# Mayfly_v1p1_revA.net
KiCad netlist of a schematic drawn in EAGLE
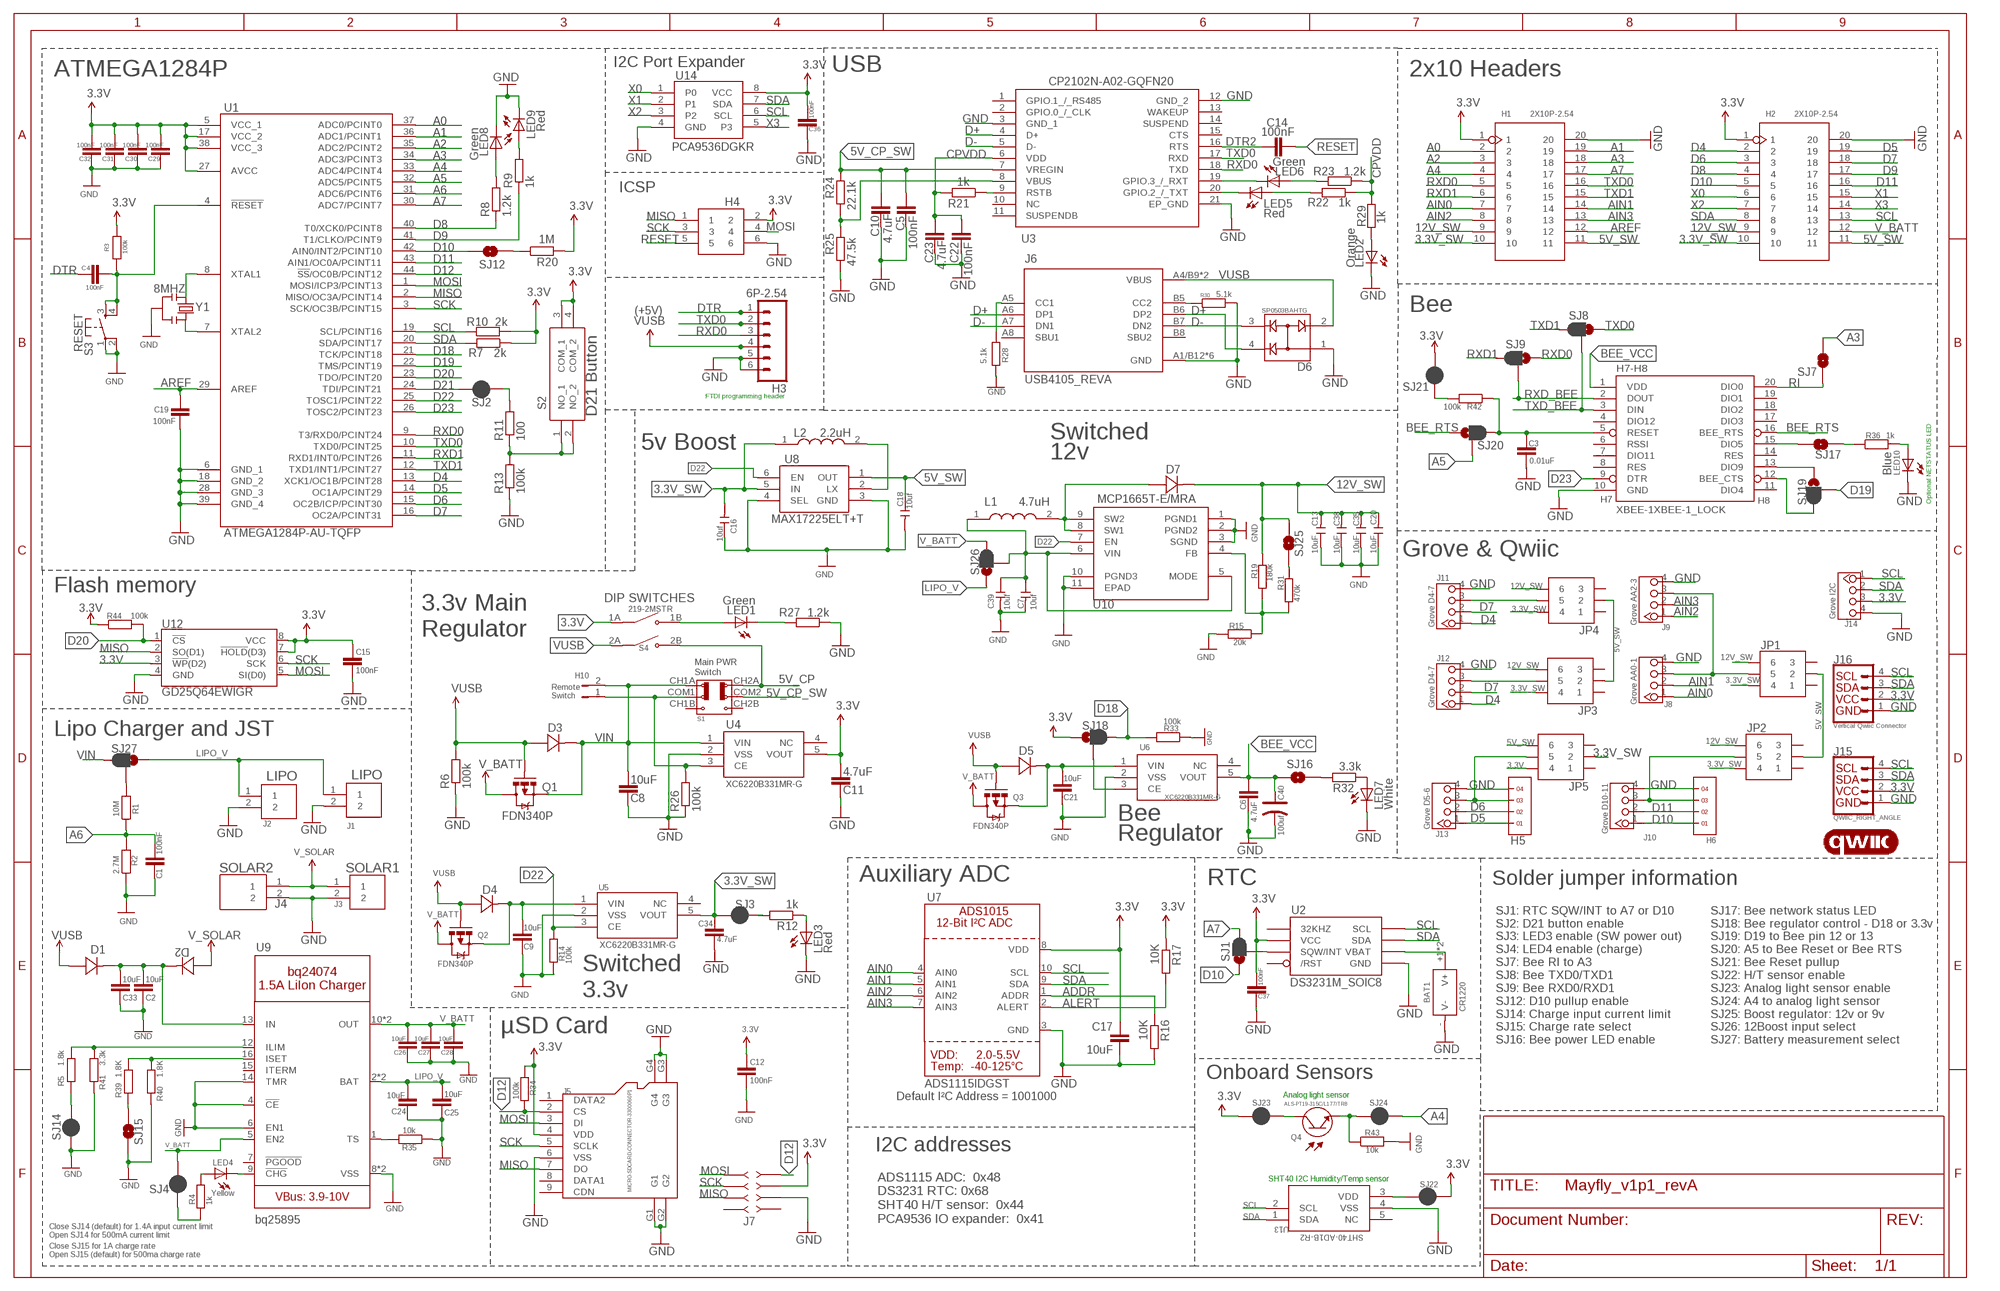
[diagram p0: schematic, sheet 1]

(export (version "E")
  (design (tool "Eeschema 10.0.6"))
  (components
    (comp (ref "BAT1")
      (value "CR1220")
      (footprint "eagle-import:BAT2P-13.5-CR1220")
      (libsource (lib "eagle-import") (part "DIP-BATTERY-CELL-HOLDER(1220)"))
    )
    (comp (ref "C1")
      (value "100nF")
      (footprint "eagle-import:C0603")
      (libsource (lib "eagle-import") (part "C_0603"))
    )
    (comp (ref "C2")
      (value "10uF")
      (footprint "eagle-import:C0603")
      (libsource (lib "eagle-import") (part "C_0603"))
    )
    (comp (ref "C3")
      (value "0.01uF")
      (footprint "eagle-import:C0603")
      (libsource (lib "eagle-import") (part "C_0603"))
    )
    (comp (ref "C4")
      (value "100nF")
      (footprint "eagle-import:C0603")
      (libsource (lib "eagle-import") (part "C_0603"))
    )
    (comp (ref "C5")
      (value "100nF")
      (footprint "eagle-import:C0603")
      (libsource (lib "eagle-import") (part "C_0603"))
    )
    (comp (ref "C6")
      (value "4.7uF")
      (footprint "eagle-import:C0603")
      (libsource (lib "eagle-import") (part "C_0603"))
    )
    (comp (ref "C7")
      (value "10uf")
      (footprint "eagle-import:C0805")
      (fields (field (name "MPN") "CC0805MKX5R5BB226"))
      (libsource (lib "eagle-import") (part "CERAMIC-22UF-6.3V-20%-X5R(0805)"))
    )
    (comp (ref "C8")
      (value "10uF")
      (footprint "eagle-import:C0603")
      (libsource (lib "eagle-import") (part "C_0603"))
    )
    (comp (ref "C9")
      (value "10uF")
      (footprint "eagle-import:C0603")
      (libsource (lib "eagle-import") (part "C_0603"))
    )
    (comp (ref "C10")
      (value "4.7uF")
      (footprint "eagle-import:C0603")
      (libsource (lib "eagle-import") (part "C_0603"))
    )
    (comp (ref "C11")
      (value "4.7uF")
      (footprint "eagle-import:C0603")
      (libsource (lib "eagle-import") (part "C_0603"))
    )
    (comp (ref "C12")
      (value "100nF")
      (footprint "eagle-import:C0603")
      (libsource (lib "eagle-import") (part "C_0603"))
    )
    (comp (ref "C13")
      (value "10uF")
      (footprint "eagle-import:C1206")
      (libsource (lib "eagle-import") (part "CERAMIC-22UF-16V-10%-X7R(1206)"))
    )
    (comp (ref "C14")
      (value "100nF")
      (footprint "eagle-import:C0603")
      (libsource (lib "eagle-import") (part "C_0603"))
    )
    (comp (ref "C15")
      (value "100nF")
      (footprint "eagle-import:C0402")
      (libsource (lib "eagle-import") (part "C_0402"))
    )
    (comp (ref "C16")
      (value "10uf")
      (footprint "eagle-import:C0603")
      (fields (field (name "MPN") "CC0603KRX5R6BB106"))
      (libsource (lib "eagle-import") (part "CERAMIC-10UF-10V-10%-X5R(0603)"))
    )
    (comp (ref "C17")
      (value "10uF")
      (footprint "eagle-import:C0603")
      (libsource (lib "eagle-import") (part "C_0603"))
    )
    (comp (ref "C18")
      (value "10uf")
      (footprint "eagle-import:C0603")
      (fields (field (name "MPN") "CC0603KRX5R6BB106"))
      (libsource (lib "eagle-import") (part "CERAMIC-10UF-10V-10%-X5R(0603)"))
    )
    (comp (ref "C19")
      (value "100nF")
      (footprint "eagle-import:C0402")
      (libsource (lib "eagle-import") (part "C_0402"))
    )
    (comp (ref "C20")
      (value "10uF")
      (footprint "eagle-import:C1206")
      (libsource (lib "eagle-import") (part "CERAMIC-22UF-16V-10%-X7R(1206)"))
    )
    (comp (ref "C21")
      (value "10uF")
      (footprint "eagle-import:C0603")
      (libsource (lib "eagle-import") (part "C_0603"))
    )
    (comp (ref "C22")
      (value "100nF")
      (footprint "eagle-import:C0603")
      (libsource (lib "eagle-import") (part "C_0603"))
    )
    (comp (ref "C23")
      (value "4.7uF")
      (footprint "eagle-import:C0603")
      (libsource (lib "eagle-import") (part "C_0603"))
    )
    (comp (ref "C24")
      (value "10uF")
      (footprint "eagle-import:C0603")
      (libsource (lib "eagle-import") (part "C_0603"))
    )
    (comp (ref "C25")
      (value "10uF")
      (footprint "eagle-import:C0603")
      (libsource (lib "eagle-import") (part "C_0603"))
    )
    (comp (ref "C26")
      (value "10uF")
      (footprint "eagle-import:C0603")
      (libsource (lib "eagle-import") (part "C_0603"))
    )
    (comp (ref "C27")
      (value "10uF")
      (footprint "eagle-import:C0603")
      (libsource (lib "eagle-import") (part "C_0603"))
    )
    (comp (ref "C28")
      (value "10uF")
      (footprint "eagle-import:C0603")
      (libsource (lib "eagle-import") (part "C_0603"))
    )
    (comp (ref "C29")
      (value "100nF")
      (footprint "eagle-import:C0603")
      (libsource (lib "eagle-import") (part "C_0603"))
    )
    (comp (ref "C30")
      (value "100nF")
      (footprint "eagle-import:C0603")
      (libsource (lib "eagle-import") (part "C_0603"))
    )
    (comp (ref "C31")
      (value "100nF")
      (footprint "eagle-import:C0603")
      (libsource (lib "eagle-import") (part "C_0603"))
    )
    (comp (ref "C32")
      (value "100nF")
      (footprint "eagle-import:C0603")
      (libsource (lib "eagle-import") (part "C_0603"))
    )
    (comp (ref "C33")
      (value "10uF")
      (footprint "eagle-import:C0603")
      (libsource (lib "eagle-import") (part "C_0603"))
    )
    (comp (ref "C34")
      (value "4.7uF")
      (footprint "eagle-import:C0603")
      (libsource (lib "eagle-import") (part "C_0603"))
    )
    (comp (ref "C35")
      (value "10uF")
      (footprint "eagle-import:C1206")
      (libsource (lib "eagle-import") (part "CERAMIC-22UF-16V-10%-X7R(1206)"))
    )
    (comp (ref "C36")
      (value "100nF")
      (footprint "eagle-import:C0603")
      (libsource (lib "eagle-import") (part "C_0603"))
    )
    (comp (ref "C37")
      (value "100nF")
      (footprint "eagle-import:C0603")
      (libsource (lib "eagle-import") (part "C_0603"))
    )
    (comp (ref "C38")
      (value "10uF")
      (footprint "eagle-import:C1206")
      (libsource (lib "eagle-import") (part "CERAMIC-22UF-16V-10%-X7R(1206)"))
    )
    (comp (ref "C39")
      (value "10uf")
      (footprint "eagle-import:C0805")
      (fields (field (name "MPN") "CC0805MKX5R5BB226"))
      (libsource (lib "eagle-import") (part "CERAMIC-22UF-6.3V-20%-X5R(0805)"))
    )
    (comp (ref "C40")
      (value "100uf")
      (footprint "eagle-import:AVX-B")
      (fields (field (name "MPN") "TAJB107M010#NJ"))
      (libsource (lib "eagle-import") (part "TANTALUM-SMD-100UF-10V(AVX-B)"))
    )
    (comp (ref "D1")
      (value "MSS2P2-M3/89A")
      (footprint "eagle-import:DIODE_MSP3V3")
      (libsource (lib "eagle-import") (part "MSS2P2-M3/89A"))
    )
    (comp (ref "D2")
      (value "MSS2P2-M3/89A")
      (footprint "eagle-import:DIODE_MSP3V3")
      (libsource (lib "eagle-import") (part "MSS2P2-M3/89A"))
    )
    (comp (ref "D3")
      (value "MSS2P2-M3/89A")
      (footprint "eagle-import:DIODE_MSP3V3")
      (libsource (lib "eagle-import") (part "MSS2P2-M3/89A"))
    )
    (comp (ref "D4")
      (value "MSS2P2-M3/89A")
      (footprint "eagle-import:DIODE_MSP3V3")
      (libsource (lib "eagle-import") (part "MSS2P2-M3/89A"))
    )
    (comp (ref "D5")
      (value "MSS2P2-M3/89A")
      (footprint "eagle-import:DIODE_MSP3V3")
      (libsource (lib "eagle-import") (part "MSS2P2-M3/89A"))
    )
    (comp (ref "D6")
      (value "SP0503BAHTG")
      (footprint "eagle-import:SOT143")
      (fields (field (name "DIGI-KEY_PART_NUMBER") "F2715CT-ND") (field (name "MF") "Littelfuse Inc."))
      (libsource (lib "eagle-import") (part "SP0503BAHTG"))
    )
    (comp (ref "D7")
      (value "MSS2P2-M3/89A")
      (footprint "eagle-import:DIODE_MSP3V3")
      (libsource (lib "eagle-import") (part "MSS2P2-M3/89A"))
    )
    (comp (ref "H1")
      (value "2X10P-2.54")
      (footprint "eagle-import:H2X10-2.54")
      (fields (field (name "MPN") "F185-1210A0BA1"))
      (libsource (lib "eagle-import") (part "DIP-BLACK-FEMALE-HEADER(2X10P-2.54)-2.54"))
    )
    (comp (ref "H2")
      (value "2X10P-2.54")
      (footprint "eagle-import:H2X10-2.54")
      (fields (field (name "MPN") "F185-1210A0BA1"))
      (libsource (lib "eagle-import") (part "DIP-BLACK-FEMALE-HEADER(2X10P-2.54)-2.54"))
    )
    (comp (ref "H3")
      (value "6P-2.54")
      (footprint "eagle-import:1X06_FEMALE_LOCK.010")
      (libsource (lib "eagle-import") (part "M06FEMALE_LOCK"))
    )
    (comp (ref "H4")
      (value "FTSH-103-01-F-D")
      (footprint "eagle-import:FTSH-103-XX-YYY")
      (fields (field (name "MOUSER_PART_NUMBER") "200-FTSH10301FD"))
      (libsource (lib "eagle-import") (part "FTSH-103-01-F-D"))
    )
    (comp (ref "H5")
      (value "1X4")
      (footprint "eagle-import:1X4")
      (libsource (lib "eagle-import") (part "1X4"))
    )
    (comp (ref "H6")
      (value "1X4")
      (footprint "eagle-import:1X4")
      (libsource (lib "eagle-import") (part "1X4"))
    )
    (comp (ref "H7-H8")
      (value "XBEE-1XBEE-1_LOCK")
      (footprint "eagle-import:XBEE-1_LOCK")
      (libsource (lib "eagle-import") (part "XBEE-1XBEE-1_LOCK"))
    )
    (comp (ref "H10")
      (value "JUMPER-PTH-2-NO")
      (footprint "eagle-import:PTH-JUMPER-2-NO_NO_SILK")
      (libsource (lib "eagle-import") (part "JUMPER-PTH-2-NO"))
    )
    (comp (ref "J1")
      (value "JST_EPH_2PIN")
      (footprint "eagle-import:JST_EPH_B2B-PH-K-S")
      (libsource (lib "eagle-import") (part "JST_EPH_2PIN"))
    )
    (comp (ref "J2")
      (value "JST_EPH_2PIN")
      (footprint "eagle-import:JST_EPH_B2B-PH-K-S")
      (libsource (lib "eagle-import") (part "JST_EPH_2PIN"))
    )
    (comp (ref "J3")
      (value "JST_EPH_2PIN")
      (footprint "eagle-import:JST_EPH_B2B-PH-K-S")
      (libsource (lib "eagle-import") (part "JST_EPH_2PIN"))
    )
    (comp (ref "J4")
      (value "1778557")
      (footprint "eagle-import:SHDR2W70P0X250_1X2_670X500X765")
      (fields (field (name "MOUSER_PART_NUMBER") "651-1778557"))
      (libsource (lib "eagle-import") (part "1778557"))
    )
    (comp (ref "J5")
      (value "MICRO-SDCARD-CONNECTOR-3300060P1")
      (footprint "eagle-import:9P-SMD-W-RING")
      (libsource (lib "eagle-import") (part "MICRO-SDCARD-CONNECTOR-3300060P1"))
    )
    (comp (ref "J6")
      (value "USB4105_REVA")
      (footprint "eagle-import:GCT_USB4105_REVA")
      (fields (field (name "MF") "Global Connector Technology") (field (name "MP") "USB4105"))
      (libsource (lib "eagle-import") (part "USB4105_REVA"))
    )
    (comp (ref "J7")
      (value "79107-08_S")
      (footprint "eagle-import:79107-08")
      (libsource (lib "eagle-import") (part "79107-08_S"))
    )
    (comp (ref "J8")
      (value "Grove AA0-1")
      (footprint "eagle-import:HW4-2.0")
      (libsource (lib "eagle-import") (part "GROVE-CONNECTOR-DIP(4P-2.0)"))
    )
    (comp (ref "J9")
      (value "Grove AA2-3")
      (footprint "eagle-import:HW4-2.0")
      (libsource (lib "eagle-import") (part "GROVE-CONNECTOR-DIP(4P-2.0)"))
    )
    (comp (ref "J10")
      (value "Grove D10-11")
      (footprint "eagle-import:HW4-2.0")
      (libsource (lib "eagle-import") (part "GROVE-CONNECTOR-DIP(4P-2.0)"))
    )
    (comp (ref "J11")
      (value "Grove D4-7")
      (footprint "eagle-import:HW4-2.0")
      (libsource (lib "eagle-import") (part "GROVE-CONNECTOR-DIP(4P-2.0)"))
    )
    (comp (ref "J12")
      (value "Grove D4-7")
      (footprint "eagle-import:HW4-2.0")
      (libsource (lib "eagle-import") (part "GROVE-CONNECTOR-DIP(4P-2.0)"))
    )
    (comp (ref "J13")
      (value "Grove D5-6")
      (footprint "eagle-import:HW4-2.0")
      (libsource (lib "eagle-import") (part "GROVE-CONNECTOR-DIP(4P-2.0)"))
    )
    (comp (ref "J14")
      (value "Grove I2C")
      (footprint "eagle-import:HW4-2.0")
      (libsource (lib "eagle-import") (part "GROVE-CONNECTOR-DIP(4P-2.0)"))
    )
    (comp (ref "J15")
      (value "QWIIC_RIGHT_ANGLE")
      (footprint "eagle-import:JST04_1MM_RA")
      (libsource (lib "eagle-import") (part "QWIIC_CONNECTORJS-1MM"))
    )
    (comp (ref "J16")
      (value "Vertical Qwiic Connector")
      (footprint "eagle-import:JST04_1MM_VERT")
      (libsource (lib "eagle-import") (part "QWIIC_CONNECTOR"))
    )
    (comp (ref "JP1")
      (value "M22-2520305")
      (footprint "eagle-import:HDRV6W50P200_2X3_600X400X525P")
      (fields (field (name "MOUSER_PART_NUMBER") "855-M22-2520305"))
      (libsource (lib "eagle-import") (part "M22-2520305"))
    )
    (comp (ref "JP2")
      (value "M22-2520305")
      (footprint "eagle-import:HDRV6W50P200_2X3_600X400X525P")
      (fields (field (name "MOUSER_PART_NUMBER") "855-M22-2520305"))
      (libsource (lib "eagle-import") (part "M22-2520305"))
    )
    (comp (ref "JP3")
      (value "M22-2520305")
      (footprint "eagle-import:HDRV6W50P200_2X3_600X400X525P")
      (fields (field (name "MOUSER_PART_NUMBER") "855-M22-2520305"))
      (libsource (lib "eagle-import") (part "M22-2520305"))
    )
    (comp (ref "JP4")
      (value "M22-2520305")
      (footprint "eagle-import:HDRV6W50P200_2X3_600X400X525P")
      (fields (field (name "MOUSER_PART_NUMBER") "855-M22-2520305"))
      (libsource (lib "eagle-import") (part "M22-2520305"))
    )
    (comp (ref "JP5")
      (value "M22-2520305")
      (footprint "eagle-import:HDRV6W50P200_2X3_600X400X525P")
      (fields (field (name "MOUSER_PART_NUMBER") "855-M22-2520305"))
      (libsource (lib "eagle-import") (part "M22-2520305"))
    )
    (comp (ref "L1")
      (value "4.7uH")
      (footprint "eagle-import:XAL4030472MEC")
      (fields
        (field (name "MANUFACTURER_PART_NUMBER") "XAL4030-472MEC")
        (field (name "MOUSER_PART_NUMBER") "994-XAL4030-472MEC")
      )
      (libsource (lib "eagle-import") (part "XAL4030-472MEC"))
    )
    (comp (ref "L2")
      (value "2.2uH")
      (footprint "eagle-import:1285ASH1R0MP2")
      (fields
        (field (name "MANUFACTURER_PART_NUMBER") "DFE201610E-2R2M=P2")
        (field (name "MOUSER_PART_NUMBER") "81-DFE201610E-2R2MP2")
      )
      (libsource (lib "eagle-import") (part "DFE201610E-2R2M=P2"))
    )
    (comp (ref "LED1")
      (value "Green")
      (footprint "eagle-import:LED-0603")
      (libsource (lib "eagle-import") (part "LED0603"))
    )
    (comp (ref "LED2")
      (value "Orange")
      (footprint "eagle-import:LED-0603")
      (libsource (lib "eagle-import") (part "LED0603"))
    )
    (comp (ref "LED3")
      (value "Red")
      (footprint "eagle-import:LED-0603")
      (libsource (lib "eagle-import") (part "LED0603"))
    )
    (comp (ref "LED4")
      (value "Yellow")
      (footprint "eagle-import:LED-0603")
      (libsource (lib "eagle-import") (part "LED0603"))
    )
    (comp (ref "LED5")
      (value "Red")
      (footprint "eagle-import:LED-0603")
      (libsource (lib "eagle-import") (part "LED0603"))
    )
    (comp (ref "LED6")
      (value "Green")
      (footprint "eagle-import:LED-0603")
      (libsource (lib "eagle-import") (part "LED0603"))
    )
    (comp (ref "LED7")
      (value "White")
      (footprint "eagle-import:LED-0603")
      (libsource (lib "eagle-import") (part "LED0603"))
    )
    (comp (ref "LED8")
      (value "Green")
      (footprint "eagle-import:LED-0603")
      (libsource (lib "eagle-import") (part "LED0603"))
    )
    (comp (ref "LED9")
      (value "Red")
      (footprint "eagle-import:LED-0603")
      (libsource (lib "eagle-import") (part "LED0603"))
    )
    (comp (ref "LED10")
      (value "Blue")
      (footprint "eagle-import:LED-0603")
      (libsource (lib "eagle-import") (part "LED0603"))
    )
    (comp (ref "LOGO4")
      (value "QWIIC_LOGO_5MM")
      (footprint "eagle-import:QWIIC_5MM")
      (libsource (lib "eagle-import") (part "QWIIC_LOGO_5MM"))
    )
    (comp (ref "Q1")
      (value "FDN340P")
      (footprint "eagle-import:SOT23-S-PADS")
      (libsource (lib "eagle-import") (part "MOSFET-P-CHANNELSMALL"))
    )
    (comp (ref "Q2")
      (value "FDN340P")
      (footprint "eagle-import:SOT23-S-PADS")
      (libsource (lib "eagle-import") (part "MOSFET-P-CHANNELSMALL"))
    )
    (comp (ref "Q3")
      (value "FDN340P")
      (footprint "eagle-import:SOT23-S-PADS")
      (libsource (lib "eagle-import") (part "MOSFET-P-CHANNELSMALL"))
    )
    (comp (ref "Q4")
      (value "ALS-PT19-315C/L177/TR8")
      (footprint "eagle-import:XDCR_ALS-PT19-315C_L177_TR8")
      (fields (field (name "MF") "Everlight"))
      (libsource (lib "eagle-import") (part "ALS-PT19-315C/L177/TR8"))
    )
    (comp (ref "R1")
      (value "10M")
      (footprint "eagle-import:R0402")
      (libsource (lib "eagle-import") (part "R_0402"))
    )
    (comp (ref "R2")
      (value "2.7M")
      (footprint "eagle-import:R0402")
      (libsource (lib "eagle-import") (part "R_0402"))
    )
    (comp (ref "R3")
      (value "100k")
      (footprint "eagle-import:R0603")
      (libsource (lib "eagle-import") (part "R_0603"))
    )
    (comp (ref "R4")
      (value "1k")
      (footprint "eagle-import:R0402")
      (libsource (lib "eagle-import") (part "R_0402"))
    )
    (comp (ref "R5")
      (value "1.8k")
      (footprint "eagle-import:R0402")
      (libsource (lib "eagle-import") (part "R_0402"))
    )
    (comp (ref "R6")
      (value "100k")
      (footprint "eagle-import:R0402")
      (libsource (lib "eagle-import") (part "R_0402"))
    )
    (comp (ref "R7")
      (value "2k")
      (footprint "eagle-import:R0603")
      (libsource (lib "eagle-import") (part "R_0603"))
    )
    (comp (ref "R8")
      (value "1.2k")
      (footprint "eagle-import:R0402")
      (libsource (lib "eagle-import") (part "R_0402"))
    )
    (comp (ref "R9")
      (value "1k")
      (footprint "eagle-import:R0402")
      (libsource (lib "eagle-import") (part "R_0402"))
    )
    (comp (ref "R10")
      (value "2k")
      (footprint "eagle-import:R0603")
      (libsource (lib "eagle-import") (part "R_0603"))
    )
    (comp (ref "R11")
      (value "100")
      (footprint "eagle-import:R0402")
      (libsource (lib "eagle-import") (part "R_0402"))
    )
    (comp (ref "R12")
      (value "1k")
      (footprint "eagle-import:R0402")
      (libsource (lib "eagle-import") (part "R_0402"))
    )
    (comp (ref "R13")
      (value "100k")
      (footprint "eagle-import:R0402")
      (libsource (lib "eagle-import") (part "R_0402"))
    )
    (comp (ref "R14")
      (value "100k")
      (footprint "eagle-import:R0402")
      (libsource (lib "eagle-import") (part "R_0402"))
    )
    (comp (ref "R15")
      (value "20k")
      (footprint "eagle-import:R0402")
      (libsource (lib "eagle-import") (part "R_0402"))
    )
    (comp (ref "R16")
      (value "10K")
      (footprint "eagle-import:R0402")
      (libsource (lib "eagle-import") (part "R_0402"))
    )
    (comp (ref "R17")
      (value "10K")
      (footprint "eagle-import:R0402")
      (libsource (lib "eagle-import") (part "R_0402"))
    )
    (comp (ref "R19")
      (value "180k")
      (footprint "eagle-import:R0402")
      (libsource (lib "eagle-import") (part "R_0402"))
    )
    (comp (ref "R20")
      (value "1M")
      (footprint "eagle-import:R0603")
      (libsource (lib "eagle-import") (part "R_0603"))
    )
    (comp (ref "R21")
      (value "1k")
      (footprint "eagle-import:R0402")
      (libsource (lib "eagle-import") (part "R_0402"))
    )
    (comp (ref "R22")
      (value "1k")
      (footprint "eagle-import:R0402")
      (libsource (lib "eagle-import") (part "R_0402"))
    )
    (comp (ref "R23")
      (value "1.2k")
      (footprint "eagle-import:R0402")
      (libsource (lib "eagle-import") (part "R_0402"))
    )
    (comp (ref "R24")
      (value "22.1k")
      (footprint "eagle-import:R0402")
      (libsource (lib "eagle-import") (part "R_0402"))
    )
    (comp (ref "R25")
      (value "47.5k")
      (footprint "eagle-import:R0402")
      (libsource (lib "eagle-import") (part "R_0402"))
    )
    (comp (ref "R26")
      (value "100k")
      (footprint "eagle-import:R0603")
      (libsource (lib "eagle-import") (part "R_0603"))
    )
    (comp (ref "R27")
      (value "1.2k")
      (footprint "eagle-import:R0402")
      (libsource (lib "eagle-import") (part "R_0402"))
    )
    (comp (ref "R28")
      (value "5.1k")
      (footprint "eagle-import:R0402")
      (libsource (lib "eagle-import") (part "R_0402"))
    )
    (comp (ref "R29")
      (value "1k")
      (footprint "eagle-import:R0402")
      (libsource (lib "eagle-import") (part "R_0402"))
    )
    (comp (ref "R30")
      (value "5.1k")
      (footprint "eagle-import:R0402")
      (libsource (lib "eagle-import") (part "R_0402"))
    )
    (comp (ref "R31")
      (value "470k")
      (footprint "eagle-import:R0402")
      (libsource (lib "eagle-import") (part "R_0402"))
    )
    (comp (ref "R32")
      (value "3.3k")
      (footprint "eagle-import:R0402")
      (libsource (lib "eagle-import") (part "R_0402"))
    )
    (comp (ref "R33")
      (value "100k")
      (footprint "eagle-import:R0402")
      (libsource (lib "eagle-import") (part "R_0402"))
    )
    (comp (ref "R34")
      (value "100k")
      (footprint "eagle-import:R0402")
      (libsource (lib "eagle-import") (part "R_0402"))
    )
    (comp (ref "R35")
      (value "10k")
      (footprint "eagle-import:R0402")
      (libsource (lib "eagle-import") (part "R_0402"))
    )
    (comp (ref "R36")
      (value "1k")
      (footprint "eagle-import:R0402")
      (libsource (lib "eagle-import") (part "R_0402"))
    )
    (comp (ref "R39")
      (value "1.8K")
      (footprint "eagle-import:R0402")
      (libsource (lib "eagle-import") (part "R_0402"))
    )
    (comp (ref "R40")
      (value "1.8K")
      (footprint "eagle-import:R0402")
      (libsource (lib "eagle-import") (part "R_0402"))
    )
    (comp (ref "R41")
      (value "3.3k")
      (footprint "eagle-import:R0402")
      (libsource (lib "eagle-import") (part "R_0402"))
    )
    (comp (ref "R42")
      (value "100k")
      (footprint "eagle-import:R0402")
      (libsource (lib "eagle-import") (part "R_0402"))
    )
    (comp (ref "R43")
      (value "10k")
      (footprint "eagle-import:R0402")
      (libsource (lib "eagle-import") (part "R_0402"))
    )
    (comp (ref "R44")
      (value "100k")
      (footprint "eagle-import:R0402")
      (libsource (lib "eagle-import") (part "R_0402"))
    )
    (comp (ref "S1")
      (value "SWITCH-2CH-6P-3010010P1")
      (footprint "eagle-import:6P-2CH-2.54-9.1X3.5X3.2+2H")
      (libsource (lib "eagle-import") (part "SWITCH-2CH-6P-3010010P1"))
    )
    (comp (ref "S2")
      (value "PTS647SK38SMTR2LFS")
      (footprint "eagle-import:PTS647SK38SMTR2LFS")
      (fields (field (name "MOUSER_PART_NUMBER") "611-PTS647SK38SMTR2L"))
      (libsource (lib "eagle-import") (part "PTS647SK38SMTR2LFS"))
    )
    (comp (ref "S3")
      (value "MOMENTARY-SWITCH-SPST-2-SMD-4.6X2.8MM")
      (footprint "eagle-import:TACTILE_SWITCH_SMD_4.6X2.8MM")
      (libsource (lib "eagle-import") (part "MOMENTARY-SWITCH-SPST-2-SMD-4.6X2.8MM"))
    )
    (comp (ref "S4")
      (value "219-2MSTR")
      (footprint "eagle-import:SW_219-2MSTR")
      (fields (field (name "DIGI-KEY_PART_NUMBER") "CT3114CT-ND") (field (name "MF") "CTS Electrocomponents"))
      (libsource (lib "eagle-import") (part "219-2MSTR"))
    )
    (comp (ref "SJ1")
      (value "JUMPER-SMT_3_1-NC_PASTE_SILK")
      (footprint "eagle-import:SMT-JUMPER_3_1-NC_PASTE_SILK")
      (libsource (lib "eagle-import") (part "JUMPER-SMT_3_1-NC_PASTE_SILK"))
    )
    (comp (ref "SJ2")
      (value "JUMPER-SMT_2_NC_PASTE_SILK")
      (footprint "eagle-import:SMT-JUMPER_2_NC_PASTE_SILK")
      (libsource (lib "eagle-import") (part "JUMPER-SMT_2_NC_PASTE_SILK"))
    )
    (comp (ref "SJ3")
      (value "JUMPER-SMT_2_NC_PASTE_SILK")
      (footprint "eagle-import:SMT-JUMPER_2_NC_PASTE_SILK")
      (libsource (lib "eagle-import") (part "JUMPER-SMT_2_NC_PASTE_SILK"))
    )
    (comp (ref "SJ4")
      (value "JUMPER-SMT_2_NC_PASTE_SILK")
      (footprint "eagle-import:SMT-JUMPER_2_NC_PASTE_SILK")
      (libsource (lib "eagle-import") (part "JUMPER-SMT_2_NC_PASTE_SILK"))
    )
    (comp (ref "SJ7")
      (value "JUMPER-SMT_2_NO_SILK")
      (footprint "eagle-import:SMT-JUMPER_2_NO_SILK")
      (libsource (lib "eagle-import") (part "JUMPER-SMT_2_NO_SILK"))
    )
    (comp (ref "SJ8")
      (value "JUMPER-SMT_3_1-NC_PASTE_SILK")
      (footprint "eagle-import:SMT-JUMPER_3_1-NC_PASTE_SILK")
      (libsource (lib "eagle-import") (part "JUMPER-SMT_3_1-NC_PASTE_SILK"))
    )
    (comp (ref "SJ9")
      (value "JUMPER-SMT_3_1-NC_PASTE_SILK")
      (footprint "eagle-import:SMT-JUMPER_3_1-NC_PASTE_SILK")
      (libsource (lib "eagle-import") (part "JUMPER-SMT_3_1-NC_PASTE_SILK"))
    )
    (comp (ref "SJ12")
      (value "SOLDERJUMPERNO")
      (footprint "eagle-import:SJ_2S-NO")
      (libsource (lib "eagle-import") (part "SOLDERJUMPERNO"))
    )
    (comp (ref "SJ14")
      (value "JUMPER-SMT_2_NC_PASTE_SILK")
      (footprint "eagle-import:SMT-JUMPER_2_NC_PASTE_SILK")
      (libsource (lib "eagle-import") (part "JUMPER-SMT_2_NC_PASTE_SILK"))
    )
    (comp (ref "SJ15")
      (value "JUMPER-SMT_2_NO_SILK")
      (footprint "eagle-import:SMT-JUMPER_2_NO_SILK")
      (libsource (lib "eagle-import") (part "JUMPER-SMT_2_NO_SILK"))
    )
    (comp (ref "SJ16")
      (value "JUMPER-SMT_2_NO_SILK")
      (footprint "eagle-import:SMT-JUMPER_2_NO_SILK")
      (libsource (lib "eagle-import") (part "JUMPER-SMT_2_NO_SILK"))
    )
    (comp (ref "SJ17")
      (value "JUMPER-SMT_2_NO_SILK")
      (footprint "eagle-import:SMT-JUMPER_2_NO_SILK")
      (libsource (lib "eagle-import") (part "JUMPER-SMT_2_NO_SILK"))
    )
    (comp (ref "SJ18")
      (value "JUMPER-SMT_3_1-NC_PASTE_SILK")
      (footprint "eagle-import:SMT-JUMPER_3_1-NC_PASTE_SILK")
      (libsource (lib "eagle-import") (part "JUMPER-SMT_3_1-NC_PASTE_SILK"))
    )
    (comp (ref "SJ19")
      (value "JUMPER-SMT_3_1-NC_PASTE_SILK")
      (footprint "eagle-import:SMT-JUMPER_3_1-NC_PASTE_SILK")
      (libsource (lib "eagle-import") (part "JUMPER-SMT_3_1-NC_PASTE_SILK"))
    )
    (comp (ref "SJ20")
      (value "JUMPER-SMT_3_1-NC_PASTE_SILK")
      (footprint "eagle-import:SMT-JUMPER_3_1-NC_PASTE_SILK")
      (libsource (lib "eagle-import") (part "JUMPER-SMT_3_1-NC_PASTE_SILK"))
    )
    (comp (ref "SJ21")
      (value "JUMPER-SMT_2_NC_PASTE_SILK")
      (footprint "eagle-import:SMT-JUMPER_2_NC_PASTE_SILK")
      (libsource (lib "eagle-import") (part "JUMPER-SMT_2_NC_PASTE_SILK"))
    )
    (comp (ref "SJ22")
      (value "JUMPER-SMT_2_NC_PASTE_SILK")
      (footprint "eagle-import:SMT-JUMPER_2_NC_PASTE_SILK")
      (libsource (lib "eagle-import") (part "JUMPER-SMT_2_NC_PASTE_SILK"))
    )
    (comp (ref "SJ23")
      (value "JUMPER-SMT_2_NC_PASTE_SILK")
      (footprint "eagle-import:SMT-JUMPER_2_NC_PASTE_SILK")
      (libsource (lib "eagle-import") (part "JUMPER-SMT_2_NC_PASTE_SILK"))
    )
    (comp (ref "SJ24")
      (value "JUMPER-SMT_2_NC_PASTE_SILK")
      (footprint "eagle-import:SMT-JUMPER_2_NC_PASTE_SILK")
      (libsource (lib "eagle-import") (part "JUMPER-SMT_2_NC_PASTE_SILK"))
    )
    (comp (ref "SJ25")
      (value "JUMPER-SMT_2_NO_SILK")
      (footprint "eagle-import:SMT-JUMPER_2_NO_SILK")
      (libsource (lib "eagle-import") (part "JUMPER-SMT_2_NO_SILK"))
    )
    (comp (ref "SJ26")
      (value "JUMPER-SMT_3_1-NC_PASTE_SILK")
      (footprint "eagle-import:SMT-JUMPER_3_1-NC_PASTE_SILK")
      (libsource (lib "eagle-import") (part "sdh_SparkFun-Jumpers_JUMPER-SMT_3_1-NC_PASTE_SILK"))
    )
    (comp (ref "SJ27")
      (value "JUMPER-SMT_3_1-NC_PASTE_SILK")
      (footprint "eagle-import:SMT-JUMPER_3_1-NC_PASTE_SILK")
      (libsource (lib "eagle-import") (part "JUMPER-SMT_3_1-NC_PASTE_SILK"))
    )
    (comp (ref "U1")
      (value "ATMEGA1284P-AU-TQFP")
      (footprint "eagle-import:QFP80P1200X1200X120-44N")
      (fields
        (field (name "MANUFACTURER_PART_NUMBER") "ATMEGA1284P-AU")
        (field (name "MOUSER_PART_NUMBER") "556-ATMEGA1284P-AU")
      )
      (libsource (lib "eagle-import") (part "ATMEGA1284P-AU-TQFP"))
    )
    (comp (ref "U2")
      (value "DS3231M_SOIC8")
      (footprint "eagle-import:SO8")
      (libsource (lib "eagle-import") (part "DS3231M_SOIC8"))
    )
    (comp (ref "U3")
      (value "CP2102N-A02-GQFN20")
      (footprint "eagle-import:CP2102NA02GQFN20")
      (fields (field (name "MOUSER_PART_NUMBER") "634-CP2102NA02GQFN20"))
      (libsource (lib "eagle-import") (part "CP2102N-A02-GQFN20"))
    )
    (comp (ref "U4")
      (value "XC6220B331MR-G")
      (footprint "eagle-import:SOT95P280X130-5N")
      (fields (field (name "MOUSER_PART_NUMBER") "865-XC6220B331MR-G"))
      (libsource (lib "eagle-import") (part "XC6220B331MR-G"))
    )
    (comp (ref "U5")
      (value "XC6220B331MR-G")
      (footprint "eagle-import:SOT95P280X130-5N")
      (fields (field (name "MOUSER_PART_NUMBER") "865-XC6220B331MR-G"))
      (libsource (lib "eagle-import") (part "XC6220B331MR-G"))
    )
    (comp (ref "U6")
      (value "XC6220B331MR-G")
      (footprint "eagle-import:SOT95P280X130-5N")
      (fields (field (name "MOUSER_PART_NUMBER") "865-XC6220B331MR-G"))
      (libsource (lib "eagle-import") (part "XC6220B331MR-G"))
    )
    (comp (ref "U7")
      (value "ADS1115IDGST")
      (footprint "eagle-import:MSOP10")
      (libsource (lib "eagle-import") (part "ADC_ADS1015"))
    )
    (comp (ref "U8")
      (value "MAX17225ELT+T")
      (footprint "eagle-import:MAX17225ELTT")
      (fields (field (name "MOUSER_PART_NUMBER") "700-MAX17225ELT+T"))
      (libsource (lib "eagle-import") (part "MAX17225ELT+T"))
    )
    (comp (ref "U9")
      (value "ADAFRUIT_POWER_BQ24074")
      (footprint "eagle-import:ADAFRUIT_POWER_QFN16_3MM")
      (libsource (lib "eagle-import") (part "ADAFRUIT_POWER_BQ24074"))
    )
    (comp (ref "U10")
      (value "MCP1665T-E/MRA")
      (footprint "eagle-import:QFN50P200X200X90-11N")
      (libsource (lib "eagle-import") (part "MCP1665T-E/MRA"))
    )
    (comp (ref "U12")
      (value "GD25Q64EWIGR")
      (footprint "eagle-import:WSON8-6X5MM")
      (libsource (lib "eagle-import") (part "W25Q32FVZP"))
    )
    (comp (ref "U13")
      (value "SHT40-AD1B-R2")
      (footprint "eagle-import:SHT4X_SEN")
      (fields (field (name "COPYRIGHT") "Copyright (C) 2018 Accelerated Designs. All rights reserved"))
      (libsource (lib "eagle-import") (part "SHT40-AD1B-R2"))
    )
    (comp (ref "U14")
      (value "PCA9536DGKR")
      (footprint "eagle-import:SOP65P490X110-8N")
      (fields (field (name "MOUSER_PART_NUMBER") "595-PCA9536DGKR"))
      (libsource (lib "eagle-import") (part "PCA9536DGKR"))
    )
    (comp (ref "Y1")
      (value "8MHZ")
      (footprint "eagle-import:X3-SMD-3.6X1.3X0.8MM")
      (fields (field (name "MPN") "CSTCE8M00G15L99-R0"))
      (libsource (lib "eagle-import") (part "SMD-RESONATOR-8MHZ-33PF-0.1%(3P-3.2X1.3MM)"))
    )
  )
  (nets
    (net (code "1") (name "/5V_CP") (class "Default")
      (node (ref "S1") (pin "CH2A") (pinfunction "CH2A_CH2A") (pintype "bidirectional"))
      (node (ref "S4") (pin "2B") (pinfunction "NO2_2B") (pintype "passive"))
    )
    (net (code "2") (name "/A0") (class "Default")
      (node (ref "H1") (pin "2") (pinfunction "2_2") (pintype "bidirectional"))
      (node (ref "U1") (pin "37") (pinfunction "ADC0/PCINT0_37") (pintype "bidirectional"))
    )
    (net (code "3") (name "/A1") (class "Default")
      (node (ref "H1") (pin "19") (pinfunction "19_19") (pintype "bidirectional"))
      (node (ref "U1") (pin "36") (pinfunction "ADC1/PCINT1_36") (pintype "bidirectional"))
    )
    (net (code "4") (name "/A2") (class "Default")
      (node (ref "H1") (pin "3") (pinfunction "3_3") (pintype "bidirectional"))
      (node (ref "U1") (pin "35") (pinfunction "ADC2/PCINT2_35") (pintype "bidirectional"))
    )
    (net (code "5") (name "/ADDR") (class "Default")
      (node (ref "R16") (pin "1") (pinfunction "1_1") (pintype "passive"))
      (node (ref "U7") (pin "1") (pinfunction "ADDR_1") (pintype "bidirectional"))
    )
    (net (code "6") (name "/AIN0") (class "Default")
      (node (ref "H1") (pin "7") (pinfunction "7_7") (pintype "bidirectional"))
      (node (ref "J8") (pin "1") (pinfunction "1_1") (pintype "bidirectional"))
      (node (ref "U7") (pin "4") (pinfunction "AIN0_4") (pintype "bidirectional"))
    )
    (net (code "7") (name "/AIN1") (class "Default")
      (node (ref "H1") (pin "14") (pinfunction "14_14") (pintype "bidirectional"))
      (node (ref "J8") (pin "2") (pinfunction "2_2") (pintype "bidirectional"))
      (node (ref "U7") (pin "5") (pinfunction "AIN1_5") (pintype "bidirectional"))
    )
    (net (code "8") (name "/AIN2") (class "Default")
      (node (ref "H1") (pin "8") (pinfunction "8_8") (pintype "bidirectional"))
      (node (ref "J9") (pin "1") (pinfunction "1_1") (pintype "bidirectional"))
      (node (ref "U7") (pin "6") (pinfunction "AIN2_6") (pintype "bidirectional"))
    )
    (net (code "9") (name "/AIN3") (class "Default")
      (node (ref "H1") (pin "13") (pinfunction "13_13") (pintype "bidirectional"))
      (node (ref "J9") (pin "2") (pinfunction "2_2") (pintype "bidirectional"))
      (node (ref "U7") (pin "7") (pinfunction "AIN3_7") (pintype "bidirectional"))
    )
    (net (code "10") (name "/ALERT") (class "Default")
      (node (ref "R17") (pin "2") (pinfunction "2_2") (pintype "passive"))
      (node (ref "U7") (pin "2") (pinfunction "ALERT_2") (pintype "bidirectional"))
    )
    (net (code "11") (name "/AREF") (class "Default")
      (node (ref "C19") (pin "2") (pinfunction "2_2") (pintype "passive"))
      (node (ref "H1") (pin "12") (pinfunction "12_12") (pintype "bidirectional"))
      (node (ref "U1") (pin "29") (pinfunction "AREF_29") (pintype "bidirectional"))
    )
    (net (code "12") (name "/BEE_RTS") (class "Default")
      (node (ref "H7-H8") (pin "16") (pinfunction "BEE_RTS_16") (pintype "input"))
      (node (ref "SJ20") (pin "1") (pinfunction "1_1") (pintype "passive"))
    )
    (net (code "13") (name "/CPVDD") (class "Default")
      (node (ref "C22") (pin "2") (pinfunction "2_2") (pintype "passive"))
      (node (ref "C23") (pin "2") (pinfunction "2_2") (pintype "passive"))
      (node (ref "R21") (pin "2") (pinfunction "2_2") (pintype "passive"))
      (node (ref "R22") (pin "1") (pinfunction "1_1") (pintype "passive"))
      (node (ref "R23") (pin "1") (pinfunction "1_1") (pintype "passive"))
      (node (ref "R29") (pin "1") (pinfunction "1_1") (pintype "passive"))
      (node (ref "U3") (pin "6") (pinfunction "VDD_6") (pintype "bidirectional"))
    )
    (net (code "14") (name "/D+") (class "Default")
      (node (ref "D6") (pin "4") (pinfunction "4_4") (pintype "passive"))
      (node (ref "J6") (pin "A6") (pinfunction "DP1_A6") (pintype "bidirectional"))
      (node (ref "J6") (pin "B6") (pinfunction "DP2_B6") (pintype "bidirectional"))
      (node (ref "U3") (pin "4") (pinfunction "D+_4") (pintype "bidirectional"))
    )
    (net (code "15") (name "/D-") (class "Default")
      (node (ref "D6") (pin "3") (pinfunction "3_3") (pintype "passive"))
      (node (ref "J6") (pin "A7") (pinfunction "DN1_A7") (pintype "bidirectional"))
      (node (ref "J6") (pin "B7") (pinfunction "DN2_B7") (pintype "bidirectional"))
      (node (ref "U3") (pin "5") (pinfunction "D-_5") (pintype "bidirectional"))
    )
    (net (code "16") (name "/D4") (class "Default")
      (node (ref "H2") (pin "2") (pinfunction "2_2") (pintype "bidirectional"))
      (node (ref "J11") (pin "1") (pinfunction "1_1") (pintype "bidirectional"))
      (node (ref "J12") (pin "1") (pinfunction "1_1") (pintype "bidirectional"))
      (node (ref "U1") (pin "13") (pinfunction "XCK1/OC1B/PCINT28_13") (pintype "bidirectional"))
    )
    (net (code "17") (name "/D5") (class "Default")
      (node (ref "H2") (pin "19") (pinfunction "19_19") (pintype "bidirectional"))
      (node (ref "H5") (pin "1") (pinfunction "1_1") (pintype "bidirectional"))
      (node (ref "J13") (pin "1") (pinfunction "1_1") (pintype "bidirectional"))
      (node (ref "U1") (pin "14") (pinfunction "OC1A/PCINT29_14") (pintype "bidirectional"))
    )
    (net (code "18") (name "/D6") (class "Default")
      (node (ref "H2") (pin "3") (pinfunction "3_3") (pintype "bidirectional"))
      (node (ref "H5") (pin "2") (pinfunction "2_2") (pintype "bidirectional"))
      (node (ref "J13") (pin "2") (pinfunction "2_2") (pintype "bidirectional"))
      (node (ref "U1") (pin "15") (pinfunction "OC2B/ICP/PCINT30_15") (pintype "bidirectional"))
    )
    (net (code "19") (name "/D7") (class "Default")
      (node (ref "H2") (pin "18") (pinfunction "18_18") (pintype "bidirectional"))
      (node (ref "J11") (pin "2") (pinfunction "2_2") (pintype "bidirectional"))
      (node (ref "J12") (pin "2") (pinfunction "2_2") (pintype "bidirectional"))
      (node (ref "U1") (pin "16") (pinfunction "OC2A/PCINT31_16") (pintype "bidirectional"))
    )
    (net (code "20") (name "/D8") (class "Default")
      (node (ref "H2") (pin "4") (pinfunction "4_4") (pintype "bidirectional"))
      (node (ref "R8") (pin "1") (pinfunction "1_1") (pintype "passive"))
      (node (ref "U1") (pin "40") (pinfunction "T0/XCK0/PCINT8_40") (pintype "bidirectional"))
    )
    (net (code "21") (name "/D9") (class "Default")
      (node (ref "H2") (pin "17") (pinfunction "17_17") (pintype "bidirectional"))
      (node (ref "R9") (pin "1") (pinfunction "1_1") (pintype "passive"))
      (node (ref "U1") (pin "41") (pinfunction "T1/CLKO/PCINT9_41") (pintype "bidirectional"))
    )
    (net (code "22") (name "/D11") (class "Default")
      (node (ref "H2") (pin "16") (pinfunction "16_16") (pintype "bidirectional"))
      (node (ref "H6") (pin "2") (pinfunction "2_2") (pintype "bidirectional"))
      (node (ref "J10") (pin "2") (pinfunction "2_2") (pintype "bidirectional"))
      (node (ref "U1") (pin "43") (pinfunction "AIN1/OC0A/PCINT11_43") (pintype "bidirectional"))
    )
    (net (code "23") (name "/D21") (class "Default")
      (node (ref "SJ2") (pin "2") (pinfunction "2_2") (pintype "passive"))
      (node (ref "U1") (pin "24") (pinfunction "TDI/PCINT21_24") (pintype "bidirectional"))
    )
    (net (code "24") (name "/DTR") (class "Default")
      (node (ref "C4") (pin "1") (pinfunction "1_1") (pintype "passive"))
      (node (ref "H3") (pin "1") (pinfunction "1_1") (pintype "passive"))
    )
    (net (code "25") (name "/DTR2") (class "Default")
      (node (ref "C14") (pin "2") (pinfunction "2_2") (pintype "passive"))
      (node (ref "U3") (pin "16") (pinfunction "RTS_16") (pintype "bidirectional"))
    )
    (net (code "26") (name "/MISO") (class "Default")
      (node (ref "H4") (pin "1") (pinfunction "1_1") (pintype "bidirectional"))
      (node (ref "J5") (pin "7") (pinfunction "DO_7") (pintype "bidirectional"))
      (node (ref "J7") (pin "6") (pinfunction "J_6") (pintype "passive"))
      (node (ref "U1") (pin "2") (pinfunction "MISO/OC3A/PCINT14_2") (pintype "bidirectional"))
      (node (ref "U12") (pin "2") (pinfunction "SO(D1)_2") (pintype "bidirectional"))
    )
    (net (code "27") (name "/MOSI") (class "Default")
      (node (ref "H4") (pin "4") (pinfunction "4_4") (pintype "bidirectional"))
      (node (ref "J5") (pin "3") (pinfunction "DI_3") (pintype "bidirectional"))
      (node (ref "J7") (pin "2") (pinfunction "J_2") (pintype "passive"))
      (node (ref "U1") (pin "1") (pinfunction "MOSI/ICP3/PCINT13_1") (pintype "bidirectional"))
      (node (ref "U12") (pin "5") (pinfunction "SI(D0)_5") (pintype "bidirectional"))
    )
    (net (code "28") (name "/RI") (class "Default")
      (node (ref "H7-H8") (pin "20") (pinfunction "DIO0_20") (pintype "bidirectional"))
      (node (ref "SJ7") (pin "1") (pinfunction "1_1") (pintype "passive"))
    )
    (net (code "29") (name "/RXD0") (class "Default")
      (node (ref "H1") (pin "5") (pinfunction "5_5") (pintype "bidirectional"))
      (node (ref "H3") (pin "3") (pinfunction "3_3") (pintype "passive"))
      (node (ref "SJ9") (pin "1") (pinfunction "1_1") (pintype "passive"))
      (node (ref "U1") (pin "9") (pinfunction "T3/RXD0/PCINT24_9") (pintype "bidirectional"))
      (node (ref "U3") (pin "18") (pinfunction "TXD_18") (pintype "bidirectional"))
    )
    (net (code "30") (name "/RXD1") (class "Default")
      (node (ref "H1") (pin "6") (pinfunction "6_6") (pintype "bidirectional"))
      (node (ref "SJ9") (pin "3") (pinfunction "3_3") (pintype "passive"))
      (node (ref "U1") (pin "11") (pinfunction "RXD1/INT0/PCINT26_11") (pintype "bidirectional"))
    )
    (net (code "31") (name "/RXD_BEE") (class "Default")
      (node (ref "H7-H8") (pin "2") (pinfunction "DOUT_2") (pintype "output"))
      (node (ref "SJ9") (pin "2") (pinfunction "2_2") (pintype "passive"))
    )
    (net (code "32") (name "/SCK") (class "Default")
      (node (ref "H4") (pin "3") (pinfunction "3_3") (pintype "bidirectional"))
      (node (ref "J5") (pin "5") (pinfunction "SCLK_5") (pintype "bidirectional"))
      (node (ref "J7") (pin "4") (pinfunction "J_4") (pintype "passive"))
      (node (ref "U1") (pin "3") (pinfunction "SCK/OC3B/PCINT15_3") (pintype "bidirectional"))
      (node (ref "U12") (pin "6") (pinfunction "SCK_6") (pintype "bidirectional"))
    )
    (net (code "33") (name "/SCL") (class "Default")
      (node (ref "H2") (pin "13") (pinfunction "13_13") (pintype "bidirectional"))
      (node (ref "J14") (pin "1") (pinfunction "1_1") (pintype "bidirectional"))
      (node (ref "J15") (pin "4") (pinfunction "4_4") (pintype "passive"))
      (node (ref "J16") (pin "4") (pinfunction "4_4") (pintype "passive"))
      (node (ref "R10") (pin "1") (pinfunction "1_1") (pintype "passive"))
      (node (ref "U1") (pin "19") (pinfunction "SCL/PCINT16_19") (pintype "bidirectional"))
      (node (ref "U13") (pin "2") (pinfunction "SCL_2") (pintype "input"))
      (node (ref "U14") (pin "6") (pinfunction "SCL_6") (pintype "bidirectional"))
      (node (ref "U2") (pin "8") (pinfunction "SCL_8") (pintype "bidirectional"))
      (node (ref "U7") (pin "10") (pinfunction "SCL_10") (pintype "bidirectional"))
    )
    (net (code "34") (name "/SDA") (class "Default")
      (node (ref "H2") (pin "8") (pinfunction "8_8") (pintype "bidirectional"))
      (node (ref "J14") (pin "2") (pinfunction "2_2") (pintype "bidirectional"))
      (node (ref "J15") (pin "3") (pinfunction "3_3") (pintype "passive"))
      (node (ref "J16") (pin "3") (pinfunction "3_3") (pintype "passive"))
      (node (ref "R7") (pin "2") (pinfunction "2_2") (pintype "passive"))
      (node (ref "U1") (pin "20") (pinfunction "SDA/PCINT17_20") (pintype "bidirectional"))
      (node (ref "U13") (pin "1") (pinfunction "SDA_1") (pintype "bidirectional"))
      (node (ref "U14") (pin "7") (pinfunction "SDA_7") (pintype "bidirectional"))
      (node (ref "U2") (pin "7") (pinfunction "SDA_7") (pintype "bidirectional"))
      (node (ref "U7") (pin "9") (pinfunction "SDA_9") (pintype "bidirectional"))
    )
    (net (code "35") (name "/TXD0") (class "Default")
      (node (ref "H1") (pin "16") (pinfunction "16_16") (pintype "bidirectional"))
      (node (ref "H3") (pin "2") (pinfunction "2_2") (pintype "passive"))
      (node (ref "SJ8") (pin "1") (pinfunction "1_1") (pintype "passive"))
      (node (ref "U1") (pin "10") (pinfunction "TXD0/PCINT25_10") (pintype "bidirectional"))
      (node (ref "U3") (pin "17") (pinfunction "RXD_17") (pintype "bidirectional"))
    )
    (net (code "36") (name "/TXD1") (class "Default")
      (node (ref "H1") (pin "15") (pinfunction "15_15") (pintype "bidirectional"))
      (node (ref "SJ8") (pin "3") (pinfunction "3_3") (pintype "passive"))
      (node (ref "U1") (pin "12") (pinfunction "TXD1/INT1/PCINT27_12") (pintype "bidirectional"))
    )
    (net (code "37") (name "/TXD_BEE") (class "Default")
      (node (ref "H7-H8") (pin "3") (pinfunction "DIN_3") (pintype "input"))
      (node (ref "SJ8") (pin "2") (pinfunction "2_2") (pintype "passive"))
    )
    (net (code "38") (name "/VIN") (class "Default")
      (node (ref "C8") (pin "2") (pinfunction "2_2") (pintype "passive"))
      (node (ref "D3") (pin "1") (pinfunction "1_1") (pintype "passive"))
      (node (ref "H10") (pin "2") (pinfunction "2_2") (pintype "passive"))
      (node (ref "Q1") (pin "2") (pinfunction "S_2") (pintype "passive"))
      (node (ref "S1") (pin "CH1A") (pinfunction "CH1A_CH1A") (pintype "bidirectional"))
      (node (ref "SJ27") (pin "3") (pinfunction "3_3") (pintype "passive"))
      (node (ref "U4") (pin "1") (pinfunction "VIN_1") (pintype "bidirectional"))
    )
    (net (code "39") (name "/X0") (class "Default")
      (node (ref "H2") (pin "6") (pinfunction "6_6") (pintype "bidirectional"))
      (node (ref "U14") (pin "1") (pinfunction "P0_1") (pintype "bidirectional"))
    )
    (net (code "40") (name "/X1") (class "Default")
      (node (ref "H2") (pin "15") (pinfunction "15_15") (pintype "bidirectional"))
      (node (ref "U14") (pin "2") (pinfunction "P1_2") (pintype "bidirectional"))
    )
    (net (code "41") (name "/X2") (class "Default")
      (node (ref "H2") (pin "7") (pinfunction "7_7") (pintype "bidirectional"))
      (node (ref "U14") (pin "3") (pinfunction "P2_3") (pintype "bidirectional"))
    )
    (net (code "42") (name "/X3") (class "Default")
      (node (ref "H2") (pin "14") (pinfunction "14_14") (pintype "bidirectional"))
      (node (ref "U14") (pin "5") (pinfunction "P3_5") (pintype "bidirectional"))
    )
    (net (code "43") (name "3.3V") (class "Default")
      (node (ref "C11") (pin "2") (pinfunction "2_2") (pintype "passive"))
      (node (ref "C12") (pin "2") (pinfunction "2_2") (pintype "passive"))
      (node (ref "C15") (pin "2") (pinfunction "2_2") (pintype "passive"))
      (node (ref "C17") (pin "1") (pinfunction "1_1") (pintype "passive"))
      (node (ref "C29") (pin "2") (pinfunction "2_2") (pintype "passive"))
      (node (ref "C30") (pin "2") (pinfunction "2_2") (pintype "passive"))
      (node (ref "C31") (pin "2") (pinfunction "2_2") (pintype "passive"))
      (node (ref "C32") (pin "2") (pinfunction "2_2") (pintype "passive"))
      (node (ref "C36") (pin "2") (pinfunction "2_2") (pintype "passive"))
      (node (ref "C37") (pin "2") (pinfunction "2_2") (pintype "passive"))
      (node (ref "H1") (pin "1") (pinfunction "1_1") (pintype "bidirectional"))
      (node (ref "H2") (pin "1") (pinfunction "1_1") (pintype "bidirectional"))
      (node (ref "H4") (pin "2") (pinfunction "2_2") (pintype "bidirectional"))
      (node (ref "J14") (pin "3") (pinfunction "3_3") (pintype "bidirectional"))
      (node (ref "J15") (pin "2") (pinfunction "2_2") (pintype "power_in"))
      (node (ref "J16") (pin "2") (pinfunction "2_2") (pintype "power_in"))
      (node (ref "J5") (pin "4") (pinfunction "VDD_4") (pintype "bidirectional"))
      (node (ref "J7") (pin "3") (pinfunction "J_3") (pintype "passive"))
      (node (ref "JP5") (pin "4") (pinfunction "4_4") (pintype "bidirectional"))
      (node (ref "R10") (pin "2") (pinfunction "2_2") (pintype "passive"))
      (node (ref "R17") (pin "1") (pinfunction "1_1") (pintype "passive"))
      (node (ref "R20") (pin "2") (pinfunction "2_2") (pintype "passive"))
      (node (ref "R3") (pin "2") (pinfunction "2_2") (pintype "passive"))
      (node (ref "R34") (pin "1") (pinfunction "1_1") (pintype "passive"))
      (node (ref "R44") (pin "1") (pinfunction "1_1") (pintype "passive"))
      (node (ref "R7") (pin "1") (pinfunction "1_1") (pintype "passive"))
      (node (ref "S2") (pin "3") (pinfunction "COM_1_3") (pintype "bidirectional"))
      (node (ref "S2") (pin "4") (pinfunction "COM_2_4") (pintype "bidirectional"))
      (node (ref "S4") (pin "1A") (pinfunction "COM1_1A") (pintype "passive"))
      (node (ref "SJ18") (pin "1") (pinfunction "1_1") (pintype "passive"))
      (node (ref "SJ21") (pin "2") (pinfunction "2_2") (pintype "passive"))
      (node (ref "SJ22") (pin "1") (pinfunction "1_1") (pintype "passive"))
      (node (ref "SJ23") (pin "1") (pinfunction "1_1") (pintype "passive"))
      (node (ref "U1") (pin "17") (pinfunction "VCC_2_17") (pintype "bidirectional"))
      (node (ref "U1") (pin "27") (pinfunction "AVCC_27") (pintype "bidirectional"))
      (node (ref "U1") (pin "38") (pinfunction "VCC_3_38") (pintype "bidirectional"))
      (node (ref "U1") (pin "5") (pinfunction "VCC_1_5") (pintype "bidirectional"))
      (node (ref "U12") (pin "3") (pinfunction "~{WP}(D2)_3") (pintype "bidirectional"))
      (node (ref "U12") (pin "7") (pinfunction "~{HOLD}(D3)_7") (pintype "bidirectional"))
      (node (ref "U12") (pin "8") (pinfunction "VCC_8") (pintype "bidirectional"))
      (node (ref "U14") (pin "8") (pinfunction "VCC_8") (pintype "bidirectional"))
      (node (ref "U2") (pin "2") (pinfunction "VCC_2") (pintype "bidirectional"))
      (node (ref "U4") (pin "5") (pinfunction "VOUT_5") (pintype "bidirectional"))
      (node (ref "U7") (pin "8") (pinfunction "VDD_8") (pintype "bidirectional"))
    )
    (net (code "44") (name "3.3V_SW") (class "Default")
      (node (ref "C16") (pin "2") (pinfunction "2_2") (pintype "passive"))
      (node (ref "C34") (pin "2") (pinfunction "2_2") (pintype "passive"))
      (node (ref "H1") (pin "10") (pinfunction "10_10") (pintype "bidirectional"))
      (node (ref "H2") (pin "10") (pinfunction "10_10") (pintype "bidirectional"))
      (node (ref "JP1") (pin "4") (pinfunction "4_4") (pintype "bidirectional"))
      (node (ref "JP2") (pin "4") (pinfunction "4_4") (pintype "bidirectional"))
      (node (ref "JP3") (pin "4") (pinfunction "4_4") (pintype "bidirectional"))
      (node (ref "JP4") (pin "4") (pinfunction "4_4") (pintype "bidirectional"))
      (node (ref "JP5") (pin "2") (pinfunction "2_2") (pintype "bidirectional"))
      (node (ref "L2") (pin "1") (pinfunction "1_1") (pintype "bidirectional"))
      (node (ref "SJ3") (pin "1") (pinfunction "1_1") (pintype "passive"))
      (node (ref "U5") (pin "5") (pinfunction "VOUT_5") (pintype "bidirectional"))
      (node (ref "U8") (pin "5") (pinfunction "IN_5") (pintype "bidirectional"))
    )
    (net (code "45") (name "5V_CP_SW") (class "Default")
      (node (ref "C10") (pin "2") (pinfunction "2_2") (pintype "passive"))
      (node (ref "C5") (pin "2") (pinfunction "2_2") (pintype "passive"))
      (node (ref "R24") (pin "2") (pinfunction "2_2") (pintype "passive"))
      (node (ref "S1") (pin "COM2") (pinfunction "COM2_COM2") (pintype "bidirectional"))
      (node (ref "U3") (pin "7") (pinfunction "VREGIN_7") (pintype "bidirectional"))
    )
    (net (code "46") (name "5V_SW") (class "Default")
      (node (ref "C18") (pin "1") (pinfunction "1_1") (pintype "passive"))
      (node (ref "H1") (pin "11") (pinfunction "11_11") (pintype "bidirectional"))
      (node (ref "H2") (pin "11") (pinfunction "11_11") (pintype "bidirectional"))
      (node (ref "JP1") (pin "2") (pinfunction "2_2") (pintype "bidirectional"))
      (node (ref "JP2") (pin "2") (pinfunction "2_2") (pintype "bidirectional"))
      (node (ref "JP3") (pin "2") (pinfunction "2_2") (pintype "bidirectional"))
      (node (ref "JP4") (pin "2") (pinfunction "2_2") (pintype "bidirectional"))
      (node (ref "JP5") (pin "6") (pinfunction "6_6") (pintype "bidirectional"))
      (node (ref "U8") (pin "1") (pinfunction "OUT_1") (pintype "bidirectional"))
    )
    (net (code "47") (name "12V_SW") (class "Default")
      (node (ref "C13") (pin "2") (pinfunction "2_2") (pintype "passive"))
      (node (ref "C20") (pin "2") (pinfunction "2_2") (pintype "passive"))
      (node (ref "C35") (pin "2") (pinfunction "2_2") (pintype "passive"))
      (node (ref "C38") (pin "2") (pinfunction "2_2") (pintype "passive"))
      (node (ref "D7") (pin "1") (pinfunction "1_1") (pintype "passive"))
      (node (ref "H1") (pin "9") (pinfunction "9_9") (pintype "bidirectional"))
      (node (ref "H2") (pin "9") (pinfunction "9_9") (pintype "bidirectional"))
      (node (ref "JP1") (pin "6") (pinfunction "6_6") (pintype "bidirectional"))
      (node (ref "JP2") (pin "6") (pinfunction "6_6") (pintype "bidirectional"))
      (node (ref "JP3") (pin "6") (pinfunction "6_6") (pintype "bidirectional"))
      (node (ref "JP4") (pin "6") (pinfunction "6_6") (pintype "bidirectional"))
      (node (ref "R19") (pin "1") (pinfunction "1_1") (pintype "passive"))
      (node (ref "SJ25") (pin "2") (pinfunction "2_2") (pintype "passive"))
    )
    (net (code "48") (name "A3") (class "Default")
      (node (ref "H1") (pin "18") (pinfunction "18_18") (pintype "bidirectional"))
      (node (ref "SJ7") (pin "2") (pinfunction "2_2") (pintype "passive"))
      (node (ref "U1") (pin "34") (pinfunction "ADC3/PCINT3_34") (pintype "bidirectional"))
    )
    (net (code "49") (name "A4") (class "Default")
      (node (ref "H1") (pin "4") (pinfunction "4_4") (pintype "bidirectional"))
      (node (ref "SJ24") (pin "2") (pinfunction "2_2") (pintype "passive"))
      (node (ref "U1") (pin "33") (pinfunction "ADC4/PCINT4_33") (pintype "bidirectional"))
    )
    (net (code "50") (name "A5") (class "Default")
      (node (ref "SJ20") (pin "2") (pinfunction "2_2") (pintype "passive"))
      (node (ref "U1") (pin "32") (pinfunction "ADC5/PCINT5_32") (pintype "bidirectional"))
    )
    (net (code "51") (name "A6") (class "Default")
      (node (ref "C1") (pin "2") (pinfunction "2_2") (pintype "passive"))
      (node (ref "R1") (pin "1") (pinfunction "1_1") (pintype "passive"))
      (node (ref "R2") (pin "2") (pinfunction "2_2") (pintype "passive"))
      (node (ref "U1") (pin "31") (pinfunction "ADC6/PCINT6_31") (pintype "bidirectional"))
    )
    (net (code "52") (name "A7") (class "Default")
      (node (ref "H1") (pin "17") (pinfunction "17_17") (pintype "bidirectional"))
      (node (ref "SJ1") (pin "3") (pinfunction "3_3") (pintype "passive"))
      (node (ref "U1") (pin "30") (pinfunction "ADC7/PCINT7_30") (pintype "bidirectional"))
    )
    (net (code "53") (name "BEE_VCC") (class "Default")
      (node (ref "C40") (pin "+") (pinfunction "+_+") (pintype "passive"))
      (node (ref "C6") (pin "2") (pinfunction "2_2") (pintype "passive"))
      (node (ref "H7-H8") (pin "1") (pinfunction "VDD_1") (pintype "power_in"))
      (node (ref "SJ16") (pin "1") (pinfunction "1_1") (pintype "passive"))
      (node (ref "U6") (pin "5") (pinfunction "VOUT_5") (pintype "bidirectional"))
    )
    (net (code "54") (name "D10") (class "Default")
      (node (ref "H2") (pin "5") (pinfunction "5_5") (pintype "bidirectional"))
      (node (ref "H6") (pin "1") (pinfunction "1_1") (pintype "bidirectional"))
      (node (ref "J10") (pin "1") (pinfunction "1_1") (pintype "bidirectional"))
      (node (ref "SJ1") (pin "1") (pinfunction "1_1") (pintype "passive"))
      (node (ref "SJ12") (pin "1") (pinfunction "1_1") (pintype "passive"))
      (node (ref "U1") (pin "42") (pinfunction "AIN0/INT2/PCINT10_42") (pintype "bidirectional"))
    )
    (net (code "55") (name "D12") (class "Default")
      (node (ref "J5") (pin "2") (pinfunction "CS_2") (pintype "bidirectional"))
      (node (ref "J7") (pin "1") (pinfunction "J_1") (pintype "passive"))
      (node (ref "R34") (pin "2") (pinfunction "2_2") (pintype "passive"))
      (node (ref "U1") (pin "44") (pinfunction "~{SS}/OC0B/PCINT12_44") (pintype "bidirectional"))
    )
    (net (code "56") (name "D18") (class "Default")
      (node (ref "R33") (pin "2") (pinfunction "2_2") (pintype "passive"))
      (node (ref "SJ18") (pin "3") (pinfunction "3_3") (pintype "passive"))
      (node (ref "U1") (pin "21") (pinfunction "TCK/PCINT18_21") (pintype "bidirectional"))
    )
    (net (code "57") (name "D19") (class "Default")
      (node (ref "SJ19") (pin "2") (pinfunction "2_2") (pintype "passive"))
      (node (ref "U1") (pin "22") (pinfunction "TMS/PCINT19_22") (pintype "bidirectional"))
    )
    (net (code "58") (name "D20") (class "Default")
      (node (ref "R44") (pin "2") (pinfunction "2_2") (pintype "passive"))
      (node (ref "U1") (pin "23") (pinfunction "TDO/PCINT20_23") (pintype "bidirectional"))
      (node (ref "U12") (pin "1") (pinfunction "~{CS}_1") (pintype "bidirectional"))
    )
    (net (code "59") (name "D22") (class "Default")
      (node (ref "R14") (pin "2") (pinfunction "2_2") (pintype "passive"))
      (node (ref "U1") (pin "25") (pinfunction "TOSC1/PCINT22_25") (pintype "bidirectional"))
      (node (ref "U10") (pin "7") (pinfunction "EN_7") (pintype "bidirectional"))
      (node (ref "U5") (pin "3") (pinfunction "CE_3") (pintype "bidirectional"))
      (node (ref "U8") (pin "6") (pinfunction "EN_6") (pintype "bidirectional"))
    )
    (net (code "60") (name "D23") (class "Default")
      (node (ref "H7-H8") (pin "9") (pinfunction "DTR_9") (pintype "bidirectional"))
      (node (ref "U1") (pin "26") (pinfunction "TOSC2/PCINT23_26") (pintype "bidirectional"))
    )
    (net (code "61") (name "GND") (class "Default")
      (node (ref "BAT1") (pin "-") (pinfunction "V-_-") (pintype "bidirectional"))
      (node (ref "C1") (pin "1") (pinfunction "1_1") (pintype "passive"))
      (node (ref "C10") (pin "1") (pinfunction "1_1") (pintype "passive"))
      (node (ref "C11") (pin "1") (pinfunction "1_1") (pintype "passive"))
      (node (ref "C12") (pin "1") (pinfunction "1_1") (pintype "passive"))
      (node (ref "C13") (pin "1") (pinfunction "1_1") (pintype "passive"))
      (node (ref "C15") (pin "1") (pinfunction "1_1") (pintype "passive"))
      (node (ref "C16") (pin "1") (pinfunction "1_1") (pintype "passive"))
      (node (ref "C17") (pin "2") (pinfunction "2_2") (pintype "passive"))
      (node (ref "C18") (pin "2") (pinfunction "2_2") (pintype "passive"))
      (node (ref "C19") (pin "1") (pinfunction "1_1") (pintype "passive"))
      (node (ref "C2") (pin "1") (pinfunction "1_1") (pintype "passive"))
      (node (ref "C20") (pin "1") (pinfunction "1_1") (pintype "passive"))
      (node (ref "C21") (pin "1") (pinfunction "1_1") (pintype "passive"))
      (node (ref "C22") (pin "1") (pinfunction "1_1") (pintype "passive"))
      (node (ref "C23") (pin "1") (pinfunction "1_1") (pintype "passive"))
      (node (ref "C24") (pin "1") (pinfunction "1_1") (pintype "passive"))
      (node (ref "C25") (pin "1") (pinfunction "1_1") (pintype "passive"))
      (node (ref "C26") (pin "1") (pinfunction "1_1") (pintype "passive"))
      (node (ref "C27") (pin "1") (pinfunction "1_1") (pintype "passive"))
      (node (ref "C28") (pin "1") (pinfunction "1_1") (pintype "passive"))
      (node (ref "C29") (pin "1") (pinfunction "1_1") (pintype "passive"))
      (node (ref "C3") (pin "1") (pinfunction "1_1") (pintype "passive"))
      (node (ref "C30") (pin "1") (pinfunction "1_1") (pintype "passive"))
      (node (ref "C31") (pin "1") (pinfunction "1_1") (pintype "passive"))
      (node (ref "C32") (pin "1") (pinfunction "1_1") (pintype "passive"))
      (node (ref "C33") (pin "1") (pinfunction "1_1") (pintype "passive"))
      (node (ref "C34") (pin "1") (pinfunction "1_1") (pintype "passive"))
      (node (ref "C35") (pin "1") (pinfunction "1_1") (pintype "passive"))
      (node (ref "C36") (pin "1") (pinfunction "1_1") (pintype "passive"))
      (node (ref "C37") (pin "1") (pinfunction "1_1") (pintype "passive"))
      (node (ref "C38") (pin "1") (pinfunction "1_1") (pintype "passive"))
      (node (ref "C39") (pin "2") (pinfunction "2_2") (pintype "passive"))
      (node (ref "C40") (pin "-") (pinfunction "-_-") (pintype "passive"))
      (node (ref "C5") (pin "1") (pinfunction "1_1") (pintype "passive"))
      (node (ref "C6") (pin "1") (pinfunction "1_1") (pintype "passive"))
      (node (ref "C7") (pin "2") (pinfunction "2_2") (pintype "passive"))
      (node (ref "C8") (pin "1") (pinfunction "1_1") (pintype "passive"))
      (node (ref "C9") (pin "1") (pinfunction "1_1") (pintype "passive"))
      (node (ref "D6") (pin "1") (pinfunction "1_1") (pintype "passive"))
      (node (ref "H1") (pin "20") (pinfunction "20_20") (pintype "bidirectional"))
      (node (ref "H2") (pin "20") (pinfunction "20_20") (pintype "bidirectional"))
      (node (ref "H3") (pin "5") (pinfunction "5_5") (pintype "passive"))
      (node (ref "H3") (pin "6") (pinfunction "6_6") (pintype "passive"))
      (node (ref "H4") (pin "6") (pinfunction "6_6") (pintype "bidirectional"))
      (node (ref "H5") (pin "4") (pinfunction "4_4") (pintype "bidirectional"))
      (node (ref "H6") (pin "4") (pinfunction "4_4") (pintype "bidirectional"))
      (node (ref "H7-H8") (pin "10") (pinfunction "GND_10") (pintype "power_in"))
      (node (ref "J1") (pin "2") (pinfunction "2_2") (pintype "bidirectional"))
      (node (ref "J10") (pin "4") (pinfunction "4_4") (pintype "bidirectional"))
      (node (ref "J11") (pin "4") (pinfunction "4_4") (pintype "bidirectional"))
      (node (ref "J12") (pin "4") (pinfunction "4_4") (pintype "bidirectional"))
      (node (ref "J13") (pin "4") (pinfunction "4_4") (pintype "bidirectional"))
      (node (ref "J14") (pin "4") (pinfunction "4_4") (pintype "bidirectional"))
      (node (ref "J15") (pin "1") (pinfunction "1_1") (pintype "power_in"))
      (node (ref "J16") (pin "1") (pinfunction "1_1") (pintype "power_in"))
      (node (ref "J2") (pin "2") (pinfunction "2_2") (pintype "bidirectional"))
      (node (ref "J3") (pin "2") (pinfunction "2_2") (pintype "bidirectional"))
      (node (ref "J4") (pin "2") (pinfunction "2_2") (pintype "bidirectional"))
      (node (ref "J5") (pin "6") (pinfunction "VSS_6") (pintype "bidirectional"))
      (node (ref "J5") (pin "G1") (pinfunction "G1_G1") (pintype "bidirectional"))
      (node (ref "J5") (pin "G2") (pinfunction "G2_G2") (pintype "bidirectional"))
      (node (ref "J5") (pin "G3") (pinfunction "G3_G3") (pintype "bidirectional"))
      (node (ref "J5") (pin "G4") (pinfunction "G4_G4") (pintype "bidirectional"))
      (node (ref "J6") (pin "A1/B12") (pinfunction "GND_A1/B12") (pintype "power_in"))
      (node (ref "J6") (pin "B1/A12") (pinfunction "GND_B1/A12") (pintype "power_in"))
      (node (ref "J6") (pin "G1") (pinfunction "GND_G1") (pintype "power_in"))
      (node (ref "J6") (pin "G2") (pinfunction "GND_G2") (pintype "power_in"))
      (node (ref "J6") (pin "G3") (pinfunction "GND_G3") (pintype "power_in"))
      (node (ref "J6") (pin "G4") (pinfunction "GND_G4") (pintype "power_in"))
      (node (ref "J7") (pin "5") (pinfunction "J_5") (pintype "passive"))
      (node (ref "J8") (pin "4") (pinfunction "4_4") (pintype "bidirectional"))
      (node (ref "J9") (pin "4") (pinfunction "4_4") (pintype "bidirectional"))
      (node (ref "LED10") (pin "C") (pinfunction "C_C") (pintype "passive"))
      (node (ref "LED2") (pin "C") (pinfunction "C_C") (pintype "passive"))
      (node (ref "LED3") (pin "C") (pinfunction "C_C") (pintype "passive"))
      (node (ref "LED7") (pin "C") (pinfunction "C_C") (pintype "passive"))
      (node (ref "LED8") (pin "C") (pinfunction "C_C") (pintype "passive"))
      (node (ref "LED9") (pin "C") (pinfunction "C_C") (pintype "passive"))
      (node (ref "R13") (pin "1") (pinfunction "1_1") (pintype "passive"))
      (node (ref "R14") (pin "1") (pinfunction "1_1") (pintype "passive"))
      (node (ref "R15") (pin "2") (pinfunction "2_2") (pintype "passive"))
      (node (ref "R16") (pin "2") (pinfunction "2_2") (pintype "passive"))
      (node (ref "R2") (pin "1") (pinfunction "1_1") (pintype "passive"))
      (node (ref "R25") (pin "1") (pinfunction "1_1") (pintype "passive"))
      (node (ref "R26") (pin "1") (pinfunction "1_1") (pintype "passive"))
      (node (ref "R27") (pin "1") (pinfunction "1_1") (pintype "passive"))
      (node (ref "R28") (pin "2") (pinfunction "2_2") (pintype "passive"))
      (node (ref "R30") (pin "2") (pinfunction "2_2") (pintype "passive"))
      (node (ref "R33") (pin "1") (pinfunction "1_1") (pintype "passive"))
      (node (ref "R35") (pin "1") (pinfunction "1_1") (pintype "passive"))
      (node (ref "R40") (pin "1") (pinfunction "1_1") (pintype "passive"))
      (node (ref "R41") (pin "1") (pinfunction "1_1") (pintype "passive"))
      (node (ref "R43") (pin "2") (pinfunction "2_2") (pintype "passive"))
      (node (ref "R6") (pin "1") (pinfunction "1_1") (pintype "passive"))
      (node (ref "S3") (pin "1") (pinfunction "1_1") (pintype "passive"))
      (node (ref "S3") (pin "2") (pinfunction "2_2") (pintype "passive"))
      (node (ref "SJ14") (pin "2") (pinfunction "2_2") (pintype "passive"))
      (node (ref "SJ15") (pin "1") (pinfunction "1_1") (pintype "passive"))
      (node (ref "U1") (pin "18") (pinfunction "GND_2_18") (pintype "bidirectional"))
      (node (ref "U1") (pin "28") (pinfunction "GND_3_28") (pintype "bidirectional"))
      (node (ref "U1") (pin "39") (pinfunction "GND_4_39") (pintype "bidirectional"))
      (node (ref "U1") (pin "6") (pinfunction "GND_1_6") (pintype "bidirectional"))
      (node (ref "U10") (pin "1") (pinfunction "PGND1_1") (pintype "bidirectional"))
      (node (ref "U10") (pin "10") (pinfunction "PGND3_10") (pintype "bidirectional"))
      (node (ref "U10") (pin "11") (pinfunction "EPAD_11") (pintype "bidirectional"))
      (node (ref "U10") (pin "2") (pinfunction "PGND2_2") (pintype "bidirectional"))
      (node (ref "U10") (pin "3") (pinfunction "SGND_3") (pintype "bidirectional"))
      (node (ref "U12") (pin "4") (pinfunction "GND_4") (pintype "bidirectional"))
      (node (ref "U13") (pin "4") (pinfunction "VSS_4") (pintype "passive"))
      (node (ref "U14") (pin "4") (pinfunction "GND_4") (pintype "bidirectional"))
      (node (ref "U2") (pin "5") (pinfunction "GND_5") (pintype "bidirectional"))
      (node (ref "U3") (pin "12") (pinfunction "GND_2_12") (pintype "bidirectional"))
      (node (ref "U3") (pin "21") (pinfunction "EP_GND_21") (pintype "bidirectional"))
      (node (ref "U3") (pin "3") (pinfunction "GND_1_3") (pintype "bidirectional"))
      (node (ref "U4") (pin "2") (pinfunction "VSS_2") (pintype "bidirectional"))
      (node (ref "U5") (pin "2") (pinfunction "VSS_2") (pintype "bidirectional"))
      (node (ref "U6") (pin "2") (pinfunction "VSS_2") (pintype "bidirectional"))
      (node (ref "U7") (pin "3") (pinfunction "GND_3") (pintype "bidirectional"))
      (node (ref "U8") (pin "3") (pinfunction "GND_3") (pintype "bidirectional"))
      (node (ref "U8") (pin "4") (pinfunction "SEL_4") (pintype "bidirectional"))
      (node (ref "U9") (pin "14") (pinfunction "TMR_14") (pintype "input"))
      (node (ref "U9") (pin "4") (pinfunction "~{CE}_4") (pintype "input"))
      (node (ref "U9") (pin "6") (pinfunction "EN1_6") (pintype "input"))
      (node (ref "U9") (pin "8") (pinfunction "VSS_8") (pintype "power_in"))
      (node (ref "U9") (pin "THERMAL") (pinfunction "VSS_THERMAL") (pintype "power_in"))
      (node (ref "Y1") (pin "2") (pinfunction "2_2") (pintype "passive"))
    )
    (net (code "62") (name "LIPO_V") (class "Default")
      (node (ref "C24") (pin "2") (pinfunction "2_2") (pintype "passive"))
      (node (ref "C25") (pin "2") (pinfunction "2_2") (pintype "passive"))
      (node (ref "J1") (pin "1") (pinfunction "1_1") (pintype "bidirectional"))
      (node (ref "J2") (pin "1") (pinfunction "1_1") (pintype "bidirectional"))
      (node (ref "SJ26") (pin "1") (pinfunction "1_1") (pintype "passive"))
      (node (ref "SJ27") (pin "1") (pinfunction "1_1") (pintype "passive"))
      (node (ref "U9") (pin "2") (pinfunction "BAT_2") (pintype "input"))
      (node (ref "U9") (pin "3") (pinfunction "BAT_3") (pintype "input"))
    )
    (net (code "63") (name "Net-(H5-Pad3)") (class "Default")
      (node (ref "H5") (pin "3") (pinfunction "3_3") (pintype "bidirectional"))
      (node (ref "J13") (pin "3") (pinfunction "3_3") (pintype "bidirectional"))
      (node (ref "JP5") (pin "5") (pinfunction "5_5") (pintype "bidirectional"))
    )
    (net (code "64") (name "Net-(H6-Pad3)") (class "Default")
      (node (ref "H6") (pin "3") (pinfunction "3_3") (pintype "bidirectional"))
      (node (ref "J10") (pin "3") (pinfunction "3_3") (pintype "bidirectional"))
      (node (ref "JP2") (pin "5") (pinfunction "5_5") (pintype "bidirectional"))
    )
    (net (code "65") (name "Net-(H7-H8-BEE_CTS)") (class "Default")
      (node (ref "H7-H8") (pin "12") (pinfunction "BEE_CTS_12") (pintype "output"))
      (node (ref "SJ19") (pin "3") (pinfunction "3_3") (pintype "passive"))
    )
    (net (code "66") (name "Net-(H7-H8-DIO5)") (class "Default")
      (node (ref "H7-H8") (pin "15") (pinfunction "DIO5_15") (pintype "bidirectional"))
      (node (ref "SJ17") (pin "2") (pinfunction "2_2") (pintype "passive"))
    )
    (net (code "67") (name "Net-(H7-H8-DIO9)") (class "Default")
      (node (ref "H7-H8") (pin "13") (pinfunction "DIO9_13") (pintype "bidirectional"))
      (node (ref "SJ19") (pin "1") (pinfunction "1_1") (pintype "passive"))
    )
    (net (code "68") (name "Net-(H7-H8-RESET)") (class "Default")
      (node (ref "C3") (pin "2") (pinfunction "2_2") (pintype "passive"))
      (node (ref "H7-H8") (pin "5") (pinfunction "RESET_5") (pintype "input"))
      (node (ref "R42") (pin "1") (pinfunction "1_1") (pintype "passive"))
      (node (ref "SJ20") (pin "3") (pinfunction "3_3") (pintype "passive"))
    )
    (net (code "69") (name "Net-(J6-CC1)") (class "Default")
      (node (ref "J6") (pin "A5") (pinfunction "CC1_A5") (pintype "bidirectional"))
      (node (ref "R28") (pin "1") (pinfunction "1_1") (pintype "passive"))
    )
    (net (code "70") (name "Net-(J6-CC2)") (class "Default")
      (node (ref "J6") (pin "B5") (pinfunction "CC2_B5") (pintype "bidirectional"))
      (node (ref "R30") (pin "1") (pinfunction "1_1") (pintype "passive"))
    )
    (net (code "71") (name "Net-(J8-Pad3)") (class "Default")
      (node (ref "J8") (pin "3") (pinfunction "3_3") (pintype "bidirectional"))
      (node (ref "J9") (pin "3") (pinfunction "3_3") (pintype "bidirectional"))
      (node (ref "JP1") (pin "5") (pinfunction "5_5") (pintype "bidirectional"))
    )
    (net (code "72") (name "Net-(J11-Pad3)") (class "Default")
      (node (ref "J11") (pin "3") (pinfunction "3_3") (pintype "bidirectional"))
      (node (ref "JP4") (pin "5") (pinfunction "5_5") (pintype "bidirectional"))
    )
    (net (code "73") (name "Net-(J12-Pad3)") (class "Default")
      (node (ref "J12") (pin "3") (pinfunction "3_3") (pintype "bidirectional"))
      (node (ref "JP3") (pin "5") (pinfunction "5_5") (pintype "bidirectional"))
    )
    (net (code "74") (name "Net-(LED1-PadC)") (class "Default")
      (node (ref "LED1") (pin "C") (pinfunction "C_C") (pintype "passive"))
      (node (ref "R27") (pin "2") (pinfunction "2_2") (pintype "passive"))
    )
    (net (code "75") (name "Net-(LED2-PadA)") (class "Default")
      (node (ref "LED2") (pin "A") (pinfunction "A_A") (pintype "passive"))
      (node (ref "R29") (pin "2") (pinfunction "2_2") (pintype "passive"))
    )
    (net (code "76") (name "Net-(LED3-PadA)") (class "Default")
      (node (ref "LED3") (pin "A") (pinfunction "A_A") (pintype "passive"))
      (node (ref "R12") (pin "1") (pinfunction "1_1") (pintype "passive"))
    )
    (net (code "77") (name "Net-(LED4-PadA)") (class "Default")
      (node (ref "LED4") (pin "A") (pinfunction "A_A") (pintype "passive"))
      (node (ref "R4") (pin "2") (pinfunction "2_2") (pintype "passive"))
    )
    (net (code "78") (name "Net-(LED5-PadA)") (class "Default")
      (node (ref "LED5") (pin "A") (pinfunction "A_A") (pintype "passive"))
      (node (ref "R22") (pin "2") (pinfunction "2_2") (pintype "passive"))
    )
    (net (code "79") (name "Net-(LED6-PadA)") (class "Default")
      (node (ref "LED6") (pin "A") (pinfunction "A_A") (pintype "passive"))
      (node (ref "R23") (pin "2") (pinfunction "2_2") (pintype "passive"))
    )
    (net (code "80") (name "Net-(LED7-PadA)") (class "Default")
      (node (ref "LED7") (pin "A") (pinfunction "A_A") (pintype "passive"))
      (node (ref "R32") (pin "1") (pinfunction "1_1") (pintype "passive"))
    )
    (net (code "81") (name "Net-(LED8-PadA)") (class "Default")
      (node (ref "LED8") (pin "A") (pinfunction "A_A") (pintype "passive"))
      (node (ref "R8") (pin "2") (pinfunction "2_2") (pintype "passive"))
    )
    (net (code "82") (name "Net-(LED9-PadA)") (class "Default")
      (node (ref "LED9") (pin "A") (pinfunction "A_A") (pintype "passive"))
      (node (ref "R9") (pin "2") (pinfunction "2_2") (pintype "passive"))
    )
    (net (code "83") (name "Net-(LED10-PadA)") (class "Default")
      (node (ref "LED10") (pin "A") (pinfunction "A_A") (pintype "passive"))
      (node (ref "R36") (pin "2") (pinfunction "2_2") (pintype "passive"))
    )
    (net (code "84") (name "Net-(Q2-S)") (class "Default")
      (node (ref "C9") (pin "2") (pinfunction "2_2") (pintype "passive"))
      (node (ref "D4") (pin "1") (pinfunction "1_1") (pintype "passive"))
      (node (ref "Q2") (pin "2") (pinfunction "S_2") (pintype "passive"))
      (node (ref "U5") (pin "1") (pinfunction "VIN_1") (pintype "bidirectional"))
    )
    (net (code "85") (name "Net-(Q3-S)") (class "Default")
      (node (ref "C21") (pin "2") (pinfunction "2_2") (pintype "passive"))
      (node (ref "D5") (pin "1") (pinfunction "1_1") (pintype "passive"))
      (node (ref "Q3") (pin "2") (pinfunction "S_2") (pintype "passive"))
      (node (ref "U6") (pin "1") (pinfunction "VIN_1") (pintype "bidirectional"))
    )
    (net (code "86") (name "Net-(Q4-C)") (class "Default")
      (node (ref "Q4") (pin "1") (pinfunction "C_1") (pintype "passive"))
      (node (ref "SJ23") (pin "2") (pinfunction "2_2") (pintype "passive"))
    )
    (net (code "87") (name "Net-(Q4-E)") (class "Default")
      (node (ref "Q4") (pin "2") (pinfunction "E_2") (pintype "passive"))
      (node (ref "R43") (pin "1") (pinfunction "1_1") (pintype "passive"))
      (node (ref "SJ24") (pin "1") (pinfunction "1_1") (pintype "passive"))
    )
    (net (code "88") (name "Net-(R1-Pad2)") (class "Default")
      (node (ref "R1") (pin "2") (pinfunction "2_2") (pintype "passive"))
      (node (ref "SJ27") (pin "2") (pinfunction "2_2") (pintype "passive"))
    )
    (net (code "89") (name "Net-(R4-Pad1)") (class "Default")
      (node (ref "R4") (pin "1") (pinfunction "1_1") (pintype "passive"))
      (node (ref "SJ4") (pin "2") (pinfunction "2_2") (pintype "passive"))
    )
    (net (code "90") (name "Net-(R5-Pad1)") (class "Default")
      (node (ref "R5") (pin "1") (pinfunction "1_1") (pintype "passive"))
      (node (ref "SJ14") (pin "1") (pinfunction "1_1") (pintype "passive"))
    )
    (net (code "91") (name "Net-(R11-Pad2)") (class "Default")
      (node (ref "R11") (pin "2") (pinfunction "2_2") (pintype "passive"))
      (node (ref "SJ2") (pin "1") (pinfunction "1_1") (pintype "passive"))
    )
    (net (code "92") (name "Net-(R12-Pad2)") (class "Default")
      (node (ref "R12") (pin "2") (pinfunction "2_2") (pintype "passive"))
      (node (ref "SJ3") (pin "2") (pinfunction "2_2") (pintype "passive"))
    )
    (net (code "93") (name "Net-(R20-Pad1)") (class "Default")
      (node (ref "R20") (pin "1") (pinfunction "1_1") (pintype "passive"))
      (node (ref "SJ12") (pin "2") (pinfunction "2_2") (pintype "passive"))
    )
    (net (code "94") (name "Net-(R31-Pad1)") (class "Default")
      (node (ref "R31") (pin "1") (pinfunction "1_1") (pintype "passive"))
      (node (ref "SJ25") (pin "1") (pinfunction "1_1") (pintype "passive"))
    )
    (net (code "95") (name "Net-(R32-Pad2)") (class "Default")
      (node (ref "R32") (pin "2") (pinfunction "2_2") (pintype "passive"))
      (node (ref "SJ16") (pin "2") (pinfunction "2_2") (pintype "passive"))
    )
    (net (code "96") (name "Net-(R36-Pad1)") (class "Default")
      (node (ref "R36") (pin "1") (pinfunction "1_1") (pintype "passive"))
      (node (ref "SJ17") (pin "1") (pinfunction "1_1") (pintype "passive"))
    )
    (net (code "97") (name "Net-(R39-Pad1)") (class "Default")
      (node (ref "R39") (pin "1") (pinfunction "1_1") (pintype "passive"))
      (node (ref "SJ15") (pin "2") (pinfunction "2_2") (pintype "passive"))
    )
    (net (code "98") (name "Net-(R42-Pad2)") (class "Default")
      (node (ref "R42") (pin "2") (pinfunction "2_2") (pintype "passive"))
      (node (ref "SJ21") (pin "1") (pinfunction "1_1") (pintype "passive"))
    )
    (net (code "99") (name "Net-(S2-NO_1)") (class "Default")
      (node (ref "R11") (pin "1") (pinfunction "1_1") (pintype "passive"))
      (node (ref "R13") (pin "2") (pinfunction "2_2") (pintype "passive"))
      (node (ref "S2") (pin "1") (pinfunction "NO_1_1") (pintype "bidirectional"))
      (node (ref "S2") (pin "2") (pinfunction "NO_2_2") (pintype "bidirectional"))
    )
    (net (code "100") (name "Net-(S4-NO1)") (class "Default")
      (node (ref "LED1") (pin "A") (pinfunction "A_A") (pintype "passive"))
      (node (ref "S4") (pin "1B") (pinfunction "NO1_1B") (pintype "passive"))
    )
    (net (code "101") (name "Net-(U1-XTAL1)") (class "Default")
      (node (ref "U1") (pin "8") (pinfunction "XTAL1_8") (pintype "bidirectional"))
      (node (ref "Y1") (pin "1") (pinfunction "1_1") (pintype "passive"))
    )
    (net (code "102") (name "Net-(U1-XTAL2)") (class "Default")
      (node (ref "U1") (pin "7") (pinfunction "XTAL2_7") (pintype "bidirectional"))
      (node (ref "Y1") (pin "3") (pinfunction "3_3") (pintype "passive"))
    )
    (net (code "103") (name "Net-(U2-SQW{slash}INT)") (class "Default")
      (node (ref "SJ1") (pin "2") (pinfunction "2_2") (pintype "passive"))
      (node (ref "U2") (pin "3") (pinfunction "SQW/INT_3") (pintype "bidirectional"))
    )
    (net (code "104") (name "Net-(U2-VBAT)") (class "Default")
      (node (ref "BAT1") (pin "+1") (pinfunction "V+_+1") (pintype "bidirectional"))
      (node (ref "BAT1") (pin "+2") (pinfunction "V+_+2") (pintype "bidirectional"))
      (node (ref "U2") (pin "6") (pinfunction "VBAT_6") (pintype "bidirectional"))
    )
    (net (code "105") (name "Net-(U3-GPIO.2_{slash}_TXT)") (class "Default")
      (node (ref "LED5") (pin "C") (pinfunction "C_C") (pintype "passive"))
      (node (ref "U3") (pin "20") (pinfunction "GPIO.2_/_TXT_20") (pintype "bidirectional"))
    )
    (net (code "106") (name "Net-(U3-GPIO.3_{slash}_RXT)") (class "Default")
      (node (ref "LED6") (pin "C") (pinfunction "C_C") (pintype "passive"))
      (node (ref "U3") (pin "19") (pinfunction "GPIO.3_/_RXT_19") (pintype "bidirectional"))
    )
    (net (code "107") (name "Net-(U3-RSTB)") (class "Default")
      (node (ref "R21") (pin "1") (pinfunction "1_1") (pintype "passive"))
      (node (ref "U3") (pin "9") (pinfunction "RSTB_9") (pintype "bidirectional"))
    )
    (net (code "108") (name "Net-(U3-VBUS)") (class "Default")
      (node (ref "R24") (pin "1") (pinfunction "1_1") (pintype "passive"))
      (node (ref "R25") (pin "2") (pinfunction "2_2") (pintype "passive"))
      (node (ref "U3") (pin "8") (pinfunction "VBUS_8") (pintype "bidirectional"))
    )
    (net (code "109") (name "Net-(U4-CE)") (class "Default")
      (node (ref "H10") (pin "1") (pinfunction "1_1") (pintype "passive"))
      (node (ref "R26") (pin "2") (pinfunction "2_2") (pintype "passive"))
      (node (ref "S1") (pin "COM1") (pinfunction "COM1_COM1") (pintype "bidirectional"))
      (node (ref "U4") (pin "3") (pinfunction "CE_3") (pintype "bidirectional"))
    )
    (net (code "110") (name "Net-(U6-CE)") (class "Default")
      (node (ref "SJ18") (pin "2") (pinfunction "2_2") (pintype "passive"))
      (node (ref "U6") (pin "3") (pinfunction "CE_3") (pintype "bidirectional"))
    )
    (net (code "111") (name "Net-(U8-LX)") (class "Default")
      (node (ref "L2") (pin "2") (pinfunction "2_2") (pintype "bidirectional"))
      (node (ref "U8") (pin "2") (pinfunction "LX_2") (pintype "bidirectional"))
    )
    (net (code "112") (name "Net-(U9-ILIM)") (class "Default")
      (node (ref "R41") (pin "2") (pinfunction "2_2") (pintype "passive"))
      (node (ref "R5") (pin "2") (pinfunction "2_2") (pintype "passive"))
      (node (ref "U9") (pin "12") (pinfunction "ILIM_12") (pintype "input"))
    )
    (net (code "113") (name "Net-(U9-IN)") (class "Default")
      (node (ref "C2") (pin "2") (pinfunction "2_2") (pintype "passive"))
      (node (ref "C33") (pin "2") (pinfunction "2_2") (pintype "passive"))
      (node (ref "D1") (pin "1") (pinfunction "1_1") (pintype "passive"))
      (node (ref "D2") (pin "1") (pinfunction "1_1") (pintype "passive"))
      (node (ref "U9") (pin "13") (pinfunction "IN_13") (pintype "power_in"))
    )
    (net (code "114") (name "Net-(U9-ISET)") (class "Default")
      (node (ref "R39") (pin "2") (pinfunction "2_2") (pintype "passive"))
      (node (ref "R40") (pin "2") (pinfunction "2_2") (pintype "passive"))
      (node (ref "U9") (pin "16") (pinfunction "ISET_16") (pintype "input"))
    )
    (net (code "115") (name "Net-(U9-TS)") (class "Default")
      (node (ref "R35") (pin "2") (pinfunction "2_2") (pintype "passive"))
      (node (ref "U9") (pin "1") (pinfunction "TS_1") (pintype "input"))
    )
    (net (code "116") (name "Net-(U9-~{CHG})") (class "Default")
      (node (ref "LED4") (pin "C") (pinfunction "C_C") (pintype "passive"))
      (node (ref "U9") (pin "9") (pinfunction "~{CHG}_9") (pintype "output"))
    )
    (net (code "117") (name "Net-(U10-FB)") (class "Default")
      (node (ref "R15") (pin "1") (pinfunction "1_1") (pintype "passive"))
      (node (ref "R19") (pin "2") (pinfunction "2_2") (pintype "passive"))
      (node (ref "R31") (pin "2") (pinfunction "2_2") (pintype "passive"))
      (node (ref "U10") (pin "4") (pinfunction "FB_4") (pintype "bidirectional"))
    )
    (net (code "118") (name "Net-(U10-MODE)") (class "Default")
      (node (ref "C39") (pin "1") (pinfunction "1_1") (pintype "passive"))
      (node (ref "C7") (pin "1") (pinfunction "1_1") (pintype "passive"))
      (node (ref "L1") (pin "1") (pinfunction "1_1") (pintype "bidirectional"))
      (node (ref "SJ26") (pin "2") (pinfunction "2_2") (pintype "passive"))
      (node (ref "U10") (pin "5") (pinfunction "MODE_5") (pintype "bidirectional"))
      (node (ref "U10") (pin "6") (pinfunction "VIN_6") (pintype "bidirectional"))
    )
    (net (code "119") (name "Net-(U10-SW1)") (class "Default")
      (node (ref "D7") (pin "2") (pinfunction "2_2") (pintype "passive"))
      (node (ref "L1") (pin "2") (pinfunction "2_2") (pintype "bidirectional"))
      (node (ref "U10") (pin "8") (pinfunction "SW1_8") (pintype "bidirectional"))
      (node (ref "U10") (pin "9") (pinfunction "SW2_9") (pintype "bidirectional"))
    )
    (net (code "120") (name "Net-(U13-VDD)") (class "Default")
      (node (ref "SJ22") (pin "2") (pinfunction "2_2") (pintype "passive"))
      (node (ref "U13") (pin "3") (pinfunction "VDD_3") (pintype "power_in"))
    )
    (net (code "121") (name "RESET") (class "Default")
      (node (ref "C14") (pin "1") (pinfunction "1_1") (pintype "passive"))
      (node (ref "C4") (pin "2") (pinfunction "2_2") (pintype "passive"))
      (node (ref "H4") (pin "5") (pinfunction "5_5") (pintype "bidirectional"))
      (node (ref "R3") (pin "1") (pinfunction "1_1") (pintype "passive"))
      (node (ref "S3") (pin "3") (pinfunction "3_3") (pintype "passive"))
      (node (ref "S3") (pin "4") (pinfunction "4_4") (pintype "passive"))
      (node (ref "U1") (pin "4") (pinfunction "~{RESET}_4") (pintype "bidirectional"))
    )
    (net (code "122") (name "VUSB") (class "Default")
      (node (ref "D1") (pin "2") (pinfunction "2_2") (pintype "passive"))
      (node (ref "D3") (pin "2") (pinfunction "2_2") (pintype "passive"))
      (node (ref "D4") (pin "2") (pinfunction "2_2") (pintype "passive"))
      (node (ref "D5") (pin "2") (pinfunction "2_2") (pintype "passive"))
      (node (ref "D6") (pin "2") (pinfunction "2_2") (pintype "passive"))
      (node (ref "H3") (pin "4") (pinfunction "4_4") (pintype "passive"))
      (node (ref "J6") (pin "A4/B9") (pinfunction "VBUS_A4/B9") (pintype "power_in"))
      (node (ref "J6") (pin "B4/A9") (pinfunction "VBUS_B4/A9") (pintype "power_in"))
      (node (ref "Q1") (pin "1") (pinfunction "G_1") (pintype "passive"))
      (node (ref "Q2") (pin "1") (pinfunction "G_1") (pintype "passive"))
      (node (ref "Q3") (pin "1") (pinfunction "G_1") (pintype "passive"))
      (node (ref "R6") (pin "2") (pinfunction "2_2") (pintype "passive"))
      (node (ref "S4") (pin "2A") (pinfunction "COM2_2A") (pintype "passive"))
    )
    (net (code "123") (name "V_BATT") (class "Default")
      (node (ref "C26") (pin "2") (pinfunction "2_2") (pintype "passive"))
      (node (ref "C27") (pin "2") (pinfunction "2_2") (pintype "passive"))
      (node (ref "C28") (pin "2") (pinfunction "2_2") (pintype "passive"))
      (node (ref "H2") (pin "12") (pinfunction "12_12") (pintype "bidirectional"))
      (node (ref "Q1") (pin "3") (pinfunction "D_3") (pintype "passive"))
      (node (ref "Q2") (pin "3") (pinfunction "D_3") (pintype "passive"))
      (node (ref "Q3") (pin "3") (pinfunction "D_3") (pintype "passive"))
      (node (ref "SJ26") (pin "3") (pinfunction "3_3") (pintype "passive"))
      (node (ref "SJ4") (pin "1") (pinfunction "1_1") (pintype "passive"))
      (node (ref "U9") (pin "10") (pinfunction "OUT_10") (pintype "output"))
      (node (ref "U9") (pin "11") (pinfunction "OUT_11") (pintype "output"))
      (node (ref "U9") (pin "5") (pinfunction "EN2_5") (pintype "input"))
    )
    (net (code "124") (name "V_SOLAR") (class "Default")
      (node (ref "D2") (pin "2") (pinfunction "2_2") (pintype "passive"))
      (node (ref "J3") (pin "1") (pinfunction "1_1") (pintype "bidirectional"))
      (node (ref "J4") (pin "1") (pinfunction "1_1") (pintype "bidirectional"))
    )
    (net (code "125") (name "unconnected-(H7-H8-DIO1-Pad19)") (class "Default")
      (node (ref "H7-H8") (pin "19") (pinfunction "DIO1_19") (pintype "bidirectional"))
    )
    (net (code "126") (name "unconnected-(H7-H8-DIO2-Pad18)") (class "Default")
      (node (ref "H7-H8") (pin "18") (pinfunction "DIO2_18") (pintype "bidirectional"))
    )
    (net (code "127") (name "unconnected-(H7-H8-DIO3-Pad17)") (class "Default")
      (node (ref "H7-H8") (pin "17") (pinfunction "DIO3_17") (pintype "bidirectional"))
    )
    (net (code "128") (name "unconnected-(H7-H8-DIO4-Pad11)") (class "Default")
      (node (ref "H7-H8") (pin "11") (pinfunction "DIO4_11") (pintype "bidirectional"))
    )
    (net (code "129") (name "unconnected-(H7-H8-DIO11-Pad7)") (class "Default")
      (node (ref "H7-H8") (pin "7") (pinfunction "DIO11_7") (pintype "bidirectional"))
    )
    (net (code "130") (name "unconnected-(H7-H8-DIO12-Pad4)") (class "Default")
      (node (ref "H7-H8") (pin "4") (pinfunction "DIO12_4") (pintype "bidirectional"))
    )
    (net (code "131") (name "unconnected-(H7-H8-RES-Pad8)") (class "Default")
      (node (ref "H7-H8") (pin "8") (pinfunction "RES_8") (pintype "bidirectional"))
    )
    (net (code "132") (name "unconnected-(H7-H8-RES-Pad14)") (class "Default")
      (node (ref "H7-H8") (pin "14") (pinfunction "RES_14") (pintype "bidirectional"))
    )
    (net (code "133") (name "unconnected-(H7-H8-RSSI-Pad6)") (class "Default")
      (node (ref "H7-H8") (pin "6") (pinfunction "RSSI_6") (pintype "bidirectional"))
    )
    (net (code "134") (name "unconnected-(J5-CDN-Pad9)") (class "Default")
      (node (ref "J5") (pin "9") (pinfunction "CDN_9") (pintype "bidirectional"))
    )
    (net (code "135") (name "unconnected-(J5-DATA1-Pad8)") (class "Default")
      (node (ref "J5") (pin "8") (pinfunction "DATA1_8") (pintype "bidirectional"))
    )
    (net (code "136") (name "unconnected-(J5-DATA2-Pad1)") (class "Default")
      (node (ref "J5") (pin "1") (pinfunction "DATA2_1") (pintype "bidirectional"))
    )
    (net (code "137") (name "unconnected-(J6-SBU1-PadA8)") (class "Default")
      (node (ref "J6") (pin "A8") (pinfunction "SBU1_A8") (pintype "bidirectional"))
    )
    (net (code "138") (name "unconnected-(J6-SBU2-PadB8)") (class "Default")
      (node (ref "J6") (pin "B8") (pinfunction "SBU2_B8") (pintype "bidirectional"))
    )
    (net (code "139") (name "unconnected-(J7G-J-Pad7)") (class "Default")
      (node (ref "J7") (pin "7") (pinfunction "J_7") (pintype "passive"))
    )
    (net (code "140") (name "unconnected-(J7H-J-Pad8)") (class "Default")
      (node (ref "J7") (pin "8") (pinfunction "J_8") (pintype "passive"))
    )
    (net (code "141") (name "unconnected-(JP1-Pad1)") (class "Default")
      (node (ref "JP1") (pin "1") (pinfunction "1_1") (pintype "bidirectional"))
    )
    (net (code "142") (name "unconnected-(JP1-Pad3)") (class "Default")
      (node (ref "JP1") (pin "3") (pinfunction "3_3") (pintype "bidirectional"))
    )
    (net (code "143") (name "unconnected-(JP2-Pad1)") (class "Default")
      (node (ref "JP2") (pin "1") (pinfunction "1_1") (pintype "bidirectional"))
    )
    (net (code "144") (name "unconnected-(JP2-Pad3)") (class "Default")
      (node (ref "JP2") (pin "3") (pinfunction "3_3") (pintype "bidirectional"))
    )
    (net (code "145") (name "unconnected-(JP3-Pad1)") (class "Default")
      (node (ref "JP3") (pin "1") (pinfunction "1_1") (pintype "bidirectional"))
    )
    (net (code "146") (name "unconnected-(JP3-Pad3)") (class "Default")
      (node (ref "JP3") (pin "3") (pinfunction "3_3") (pintype "bidirectional"))
    )
    (net (code "147") (name "unconnected-(JP4-Pad1)") (class "Default")
      (node (ref "JP4") (pin "1") (pinfunction "1_1") (pintype "bidirectional"))
    )
    (net (code "148") (name "unconnected-(JP4-Pad3)") (class "Default")
      (node (ref "JP4") (pin "3") (pinfunction "3_3") (pintype "bidirectional"))
    )
    (net (code "149") (name "unconnected-(JP5-Pad1)") (class "Default")
      (node (ref "JP5") (pin "1") (pinfunction "1_1") (pintype "bidirectional"))
    )
    (net (code "150") (name "unconnected-(JP5-Pad3)") (class "Default")
      (node (ref "JP5") (pin "3") (pinfunction "3_3") (pintype "bidirectional"))
    )
    (net (code "151") (name "unconnected-(S1-PadCH1B)") (class "Default")
      (node (ref "S1") (pin "CH1B") (pinfunction "CH1B_CH1B") (pintype "bidirectional"))
    )
    (net (code "152") (name "unconnected-(S1-PadCH2B)") (class "Default")
      (node (ref "S1") (pin "CH2B") (pinfunction "CH2B_CH2B") (pintype "bidirectional"))
    )
    (net (code "153") (name "unconnected-(U2-32KHZ-Pad1)") (class "Default")
      (node (ref "U2") (pin "1") (pinfunction "32KHZ_1") (pintype "bidirectional"))
    )
    (net (code "154") (name "unconnected-(U2-{slash}RST-Pad4)") (class "Default")
      (node (ref "U2") (pin "4") (pinfunction "/RST_4") (pintype "bidirectional"))
    )
    (net (code "155") (name "unconnected-(U3-CTS-Pad15)") (class "Default")
      (node (ref "U3") (pin "15") (pinfunction "CTS_15") (pintype "bidirectional"))
    )
    (net (code "156") (name "unconnected-(U3-GPIO.0_{slash}_CLK-Pad2)") (class "Default")
      (node (ref "U3") (pin "2") (pinfunction "GPIO.0_/_CLK_2") (pintype "bidirectional"))
    )
    (net (code "157") (name "unconnected-(U3-GPIO.1_{slash}_RS485-Pad1)") (class "Default")
      (node (ref "U3") (pin "1") (pinfunction "GPIO.1_/_RS485_1") (pintype "bidirectional"))
    )
    (net (code "158") (name "unconnected-(U3-NC-Pad10)") (class "Default")
      (node (ref "U3") (pin "10") (pinfunction "NC_10") (pintype "no_connect"))
    )
    (net (code "159") (name "unconnected-(U3-SUSPEND-Pad14)") (class "Default")
      (node (ref "U3") (pin "14") (pinfunction "SUSPEND_14") (pintype "bidirectional"))
    )
    (net (code "160") (name "unconnected-(U3-SUSPENDB-Pad11)") (class "Default")
      (node (ref "U3") (pin "11") (pinfunction "SUSPENDB_11") (pintype "bidirectional"))
    )
    (net (code "161") (name "unconnected-(U3-WAKEUP-Pad13)") (class "Default")
      (node (ref "U3") (pin "13") (pinfunction "WAKEUP_13") (pintype "bidirectional"))
    )
    (net (code "162") (name "unconnected-(U4-NC-Pad4)") (class "Default")
      (node (ref "U4") (pin "4") (pinfunction "NC_4") (pintype "no_connect"))
    )
    (net (code "163") (name "unconnected-(U5-NC-Pad4)") (class "Default")
      (node (ref "U5") (pin "4") (pinfunction "NC_4") (pintype "no_connect"))
    )
    (net (code "164") (name "unconnected-(U6-NC-Pad4)") (class "Default")
      (node (ref "U6") (pin "4") (pinfunction "NC_4") (pintype "no_connect"))
    )
    (net (code "165") (name "unconnected-(U9-ITERM-Pad15)") (class "Default")
      (node (ref "U9") (pin "15") (pinfunction "ITERM_15") (pintype "input"))
    )
    (net (code "166") (name "unconnected-(U9-~{PGOOD}-Pad7)") (class "Default")
      (node (ref "U9") (pin "7") (pinfunction "~{PGOOD}_7") (pintype "output"))
    )
    (net (code "167") (name "unconnected-(U13-NC-Pad5)") (class "Default")
      (node (ref "U13") (pin "5") (pinfunction "NC_5") (pintype "no_connect"))
    )
  )
)
